# L9963E_BMS_IC.net
KiCad netlist of a schematic drawn in Altium Designer
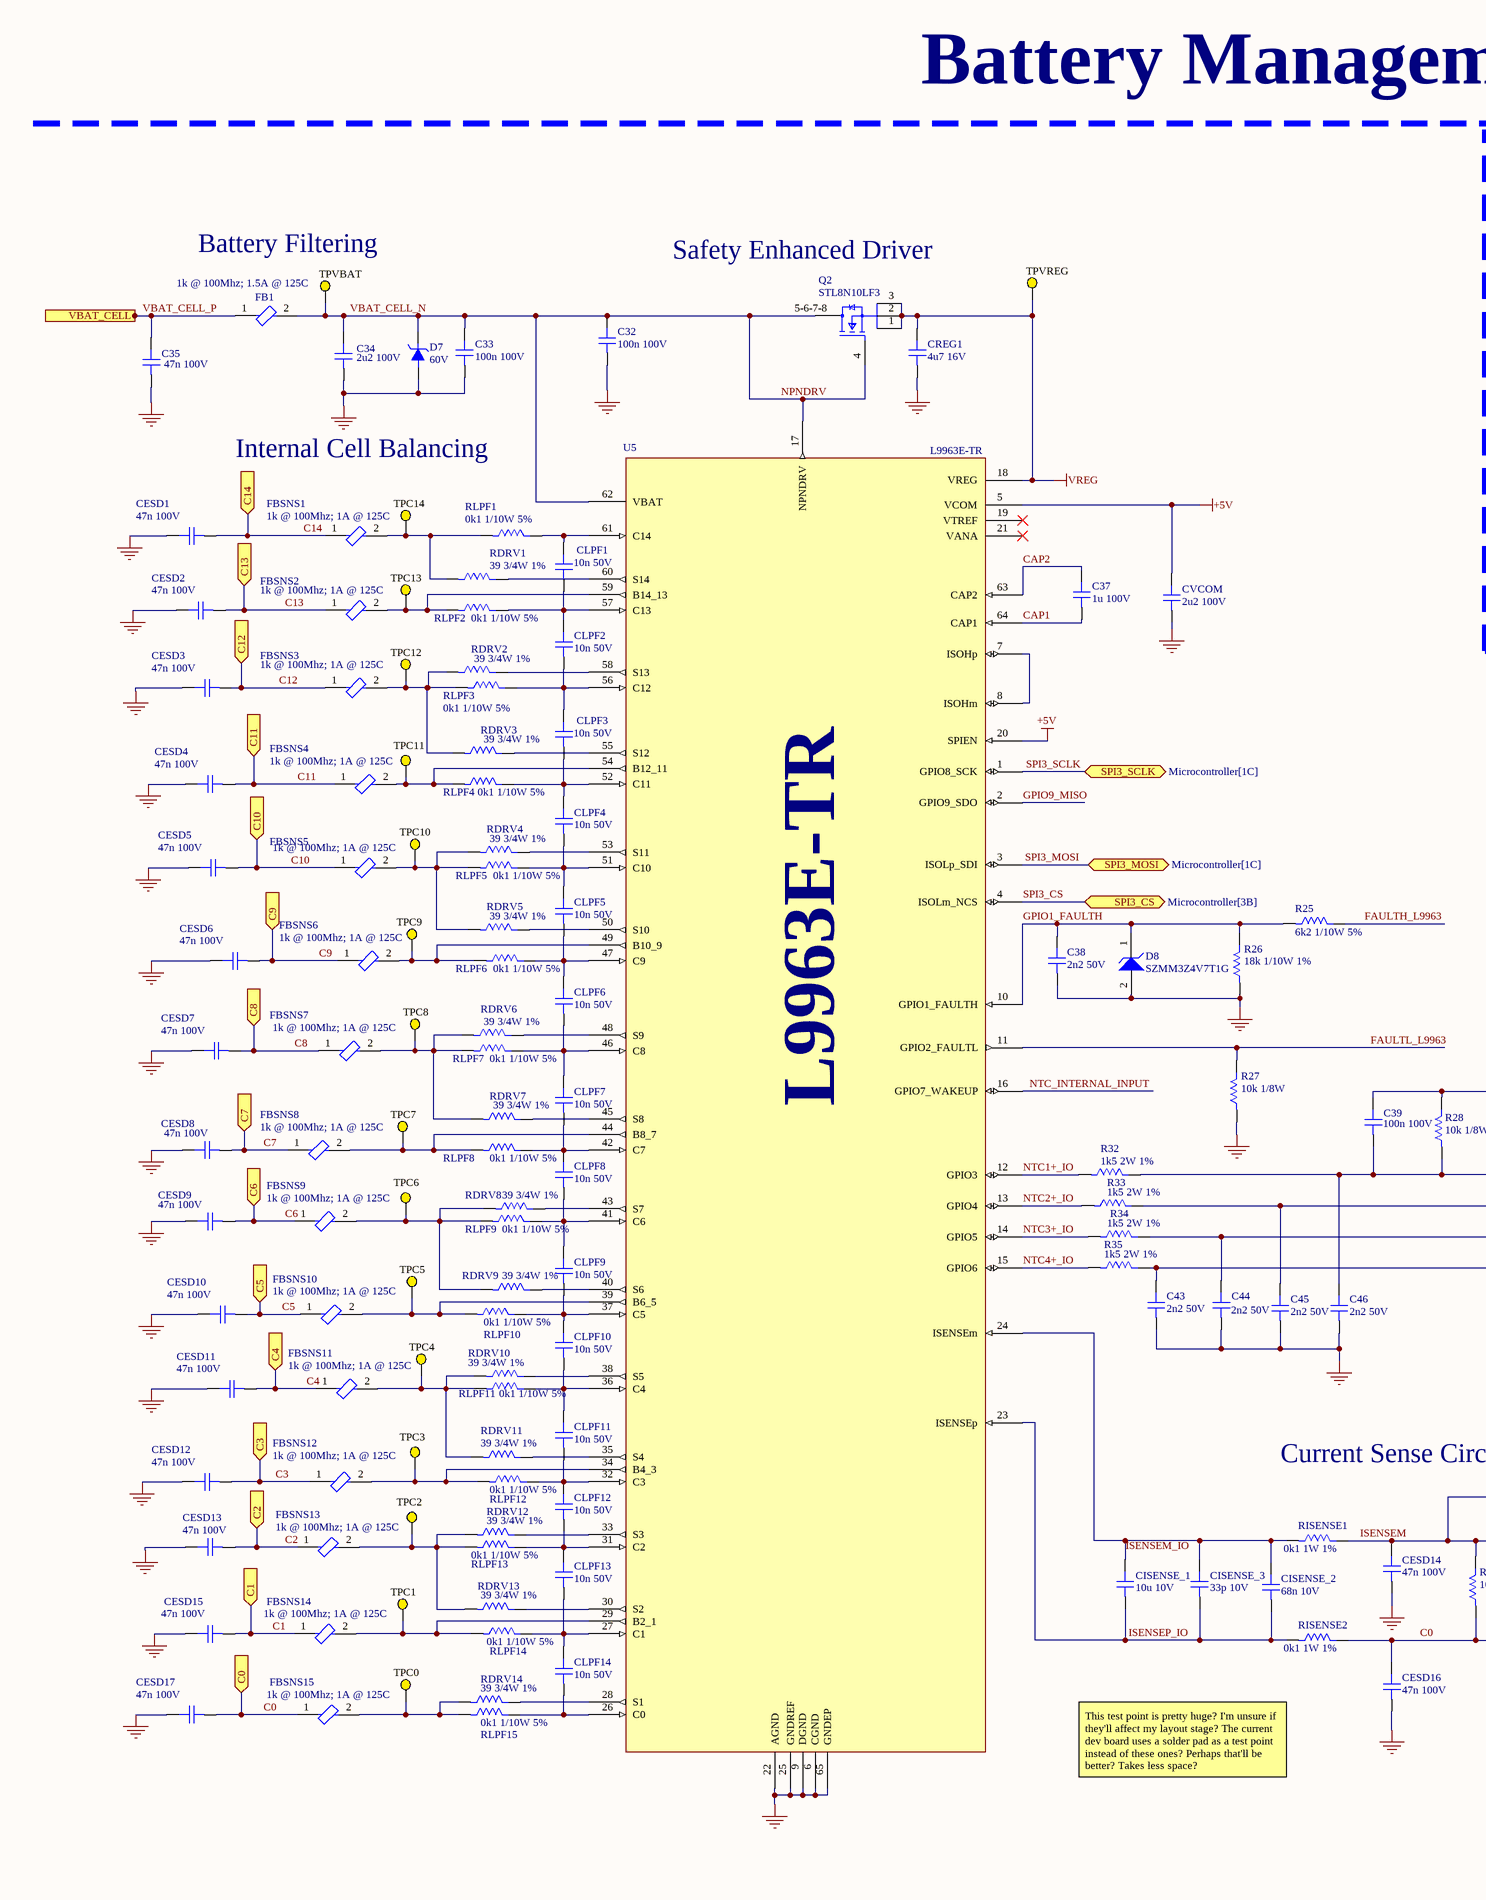
[diagram p0: L9963E_BMS_IC.SchDoc, left]
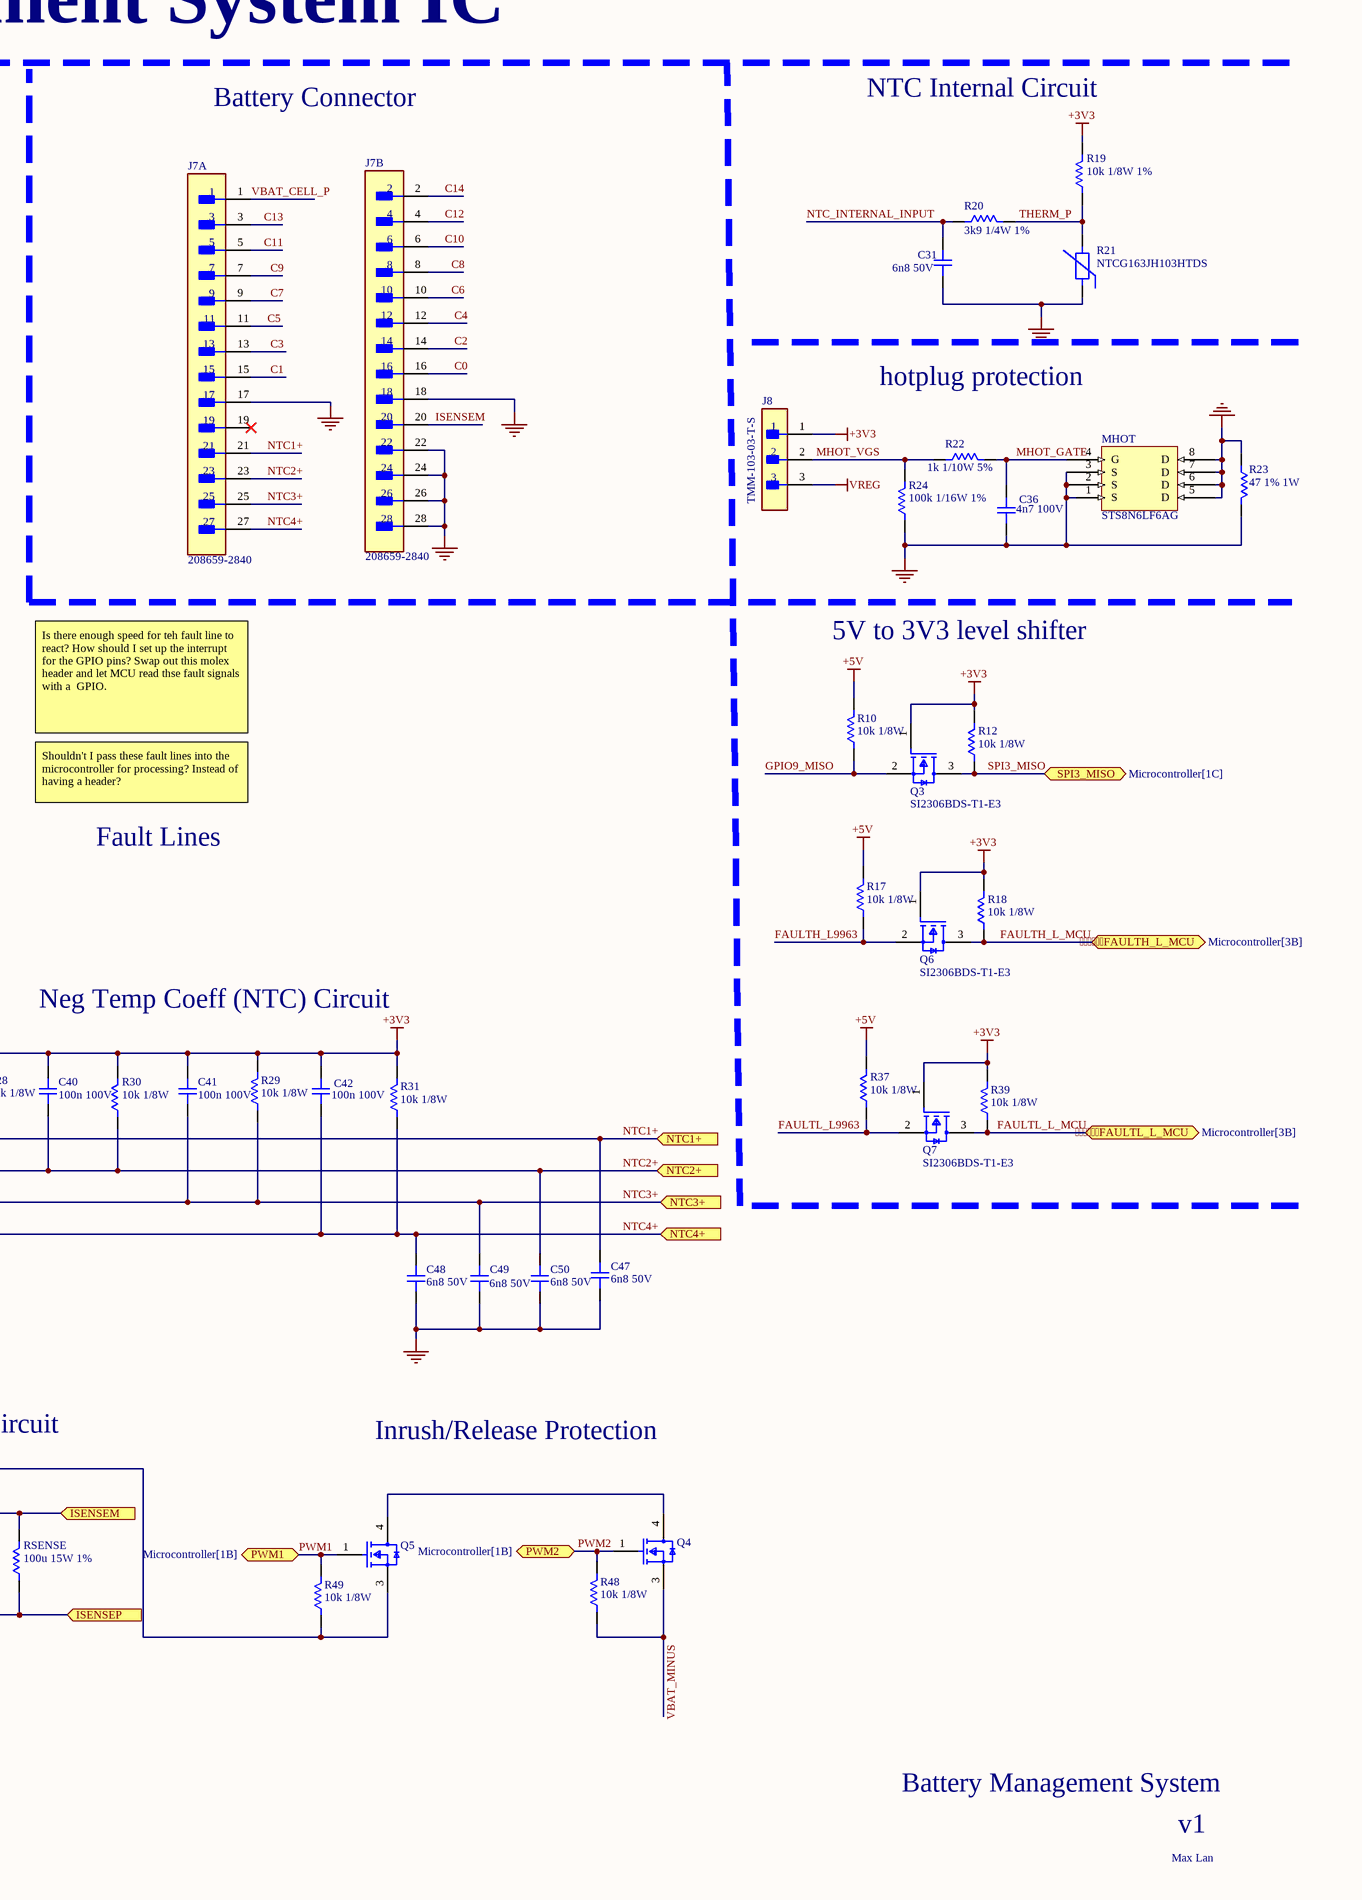
[diagram p1: L9963E_BMS_IC.SchDoc, right]

(export (version "E")
  (design (tool "Eeschema 10.0.6"))
  (components
    (comp (ref "C31")
      (value "6n8 50V")
      (footprint "CAP_0603")
      (fields
        (field (name "MANUFACTURER") "KYOCERA AVX")
        (field (name "MANUFACTURER PART NUMBER") "06035C682MAT2A")
      )
      (libsource (lib "Schematic-Lib-PhilsLab") (part "06035C682MAT2A"))
    )
    (comp (ref "C32")
      (value "100n 100V")
      (footprint "CAP_0603")
      (description "Multilayer Ceramic Capacitors MLCC - SMD/SMT 100V 0.1uF 0603 X7R 10% AECQ2")
      (fields
        (field (name "MANUFACTURER") "TAIYO YUDEN")
        (field (name "MANUFACTURER PART NUMBER") "MAJCH168BB7104KTEA01")
      )
      (libsource (lib "Schematic-Lib-PhilsLab") (part "MAJCH168BB7104KTEA01"))
    )
    (comp (ref "C33")
      (value "100n 100V")
      (footprint "CAP_0603")
      (description "Multilayer Ceramic Capacitors MLCC - SMD/SMT 100V 0.1uF 0603 X7R 10% AECQ2")
      (fields
        (field (name "MANUFACTURER") "TAIYO YUDEN")
        (field (name "MANUFACTURER PART NUMBER") "MAJCH168BB7104KTEA01")
      )
      (libsource (lib "Schematic-Lib-PhilsLab") (part "MAJCH168BB7104KTEA01"))
    )
    (comp (ref "C34")
      (value "2u2 100V")
      (footprint "CAP_1210")
      (description "Multilayer Ceramic Capacitors MLCC - SMD/SMT 100V 2.2uF X7R 1210 5% AEC-Q200")
      (fields
        (field (name "MANUFACTURER") "KEMET")
        (field (name "MANUFACTURER PART NUMBER") "C1210C225J1RACAUTO")
      )
      (libsource (lib "Schematic-Lib-PhilsLab") (part "C1210C225J1RACAUTO"))
    )
    (comp (ref "C35")
      (value "47n 100V")
      (footprint "CAP_0603")
      (description "Multilayer Ceramic Capacitors MLCC - SMD/SMT 100V 0.047uF X7R 0603 5%")
      (fields
        (field (name "MANUFACTURER") "KEMET")
        (field (name "MANUFACTURER PART NUMBER") "C0603C473J1RACTU")
      )
      (libsource (lib "Schematic-Lib-PhilsLab") (part "C0603C473J1RACTU"))
    )
    (comp (ref "C36")
      (value "4n7 100V")
      (footprint "CAP_0603")
      (description "Multilayer Ceramic Capacitors MLCC - SMD/SMT CGA 0603 100V 4700pF X7R 10% AEC-Q200")
      (fields
        (field (name "MANUFACTURER") "TDK")
        (field (name "MANUFACTURER PART NUMBER") "CGA3E2X7R2A472K080AA")
      )
      (libsource (lib "Schematic-Lib-PhilsLab") (part "CGA3E2X7R2A472K080AA"))
    )
    (comp (ref "C37")
      (value "1u 100V")
      (footprint "CAP_0603")
      (description "MLCC - SMD/SMT Commercial Grade,MLCC,0603,X7R,100V,1uF,+/-10%,0.8mm")
      (libsource (lib "Schematic-Lib-PhilsLab") (part "C1608X7R2A105K080AC"))
    )
    (comp (ref "C38")
      (value "2n2 50V")
      (footprint "CAP_0603")
      (description "Multilayer Ceramic Capacitors MLCC - SMD/SMT 50V 2200pF X7R 0603 10% AEC-Q200")
      (fields
        (field (name "MANUFACTURER") "KYOCERA AVX")
        (field (name "MANUFACTURER PART NUMBER") "KAM15AR71H222KT")
      )
      (libsource (lib "Schematic-Lib-PhilsLab") (part "KAM15AR71H222KT"))
    )
    (comp (ref "C39")
      (value "100n 100V")
      (footprint "CAP_0603")
      (description "Multilayer Ceramic Capacitors MLCC - SMD/SMT 100V 0.1uF 0603 X7R 10% AECQ2")
      (fields
        (field (name "MANUFACTURER") "TAIYO YUDEN")
        (field (name "MANUFACTURER PART NUMBER") "MAJCH168BB7104KTEA01")
      )
      (libsource (lib "Schematic-Lib-PhilsLab") (part "MAJCH168BB7104KTEA01"))
    )
    (comp (ref "C40")
      (value "100n 100V")
      (footprint "CAP_0603")
      (description "Multilayer Ceramic Capacitors MLCC - SMD/SMT 100V 0.1uF 0603 X7R 10% AECQ2")
      (fields
        (field (name "MANUFACTURER") "TAIYO YUDEN")
        (field (name "MANUFACTURER PART NUMBER") "MAJCH168BB7104KTEA01")
      )
      (libsource (lib "Schematic-Lib-PhilsLab") (part "MAJCH168BB7104KTEA01"))
    )
    (comp (ref "C41")
      (value "100n 100V")
      (footprint "CAP_0603")
      (description "Multilayer Ceramic Capacitors MLCC - SMD/SMT 100V 0.1uF 0603 X7R 10% AECQ2")
      (fields
        (field (name "MANUFACTURER") "TAIYO YUDEN")
        (field (name "MANUFACTURER PART NUMBER") "MAJCH168BB7104KTEA01")
      )
      (libsource (lib "Schematic-Lib-PhilsLab") (part "MAJCH168BB7104KTEA01"))
    )
    (comp (ref "C42")
      (value "100n 100V")
      (footprint "CAP_0603")
      (description "Multilayer Ceramic Capacitors MLCC - SMD/SMT 100V 0.1uF 0603 X7R 10% AECQ2")
      (fields
        (field (name "MANUFACTURER") "TAIYO YUDEN")
        (field (name "MANUFACTURER PART NUMBER") "MAJCH168BB7104KTEA01")
      )
      (libsource (lib "Schematic-Lib-PhilsLab") (part "MAJCH168BB7104KTEA01"))
    )
    (comp (ref "C43")
      (value "2n2 50V")
      (footprint "CAP_0603")
      (description "Multilayer Ceramic Capacitors MLCC - SMD/SMT 50V 2200pF X7R 0603 10% AEC-Q200")
      (fields
        (field (name "MANUFACTURER") "KYOCERA AVX")
        (field (name "MANUFACTURER PART NUMBER") "KAM15AR71H222KT")
      )
      (libsource (lib "Schematic-Lib-PhilsLab") (part "KAM15AR71H222KT"))
    )
    (comp (ref "C44")
      (value "2n2 50V")
      (footprint "CAP_0603")
      (description "Multilayer Ceramic Capacitors MLCC - SMD/SMT 50V 2200pF X7R 0603 10% AEC-Q200")
      (fields
        (field (name "MANUFACTURER") "KYOCERA AVX")
        (field (name "MANUFACTURER PART NUMBER") "KAM15AR71H222KT")
      )
      (libsource (lib "Schematic-Lib-PhilsLab") (part "KAM15AR71H222KT"))
    )
    (comp (ref "C45")
      (value "2n2 50V")
      (footprint "CAP_0603")
      (description "Multilayer Ceramic Capacitors MLCC - SMD/SMT 50V 2200pF X7R 0603 10% AEC-Q200")
      (fields
        (field (name "MANUFACTURER") "KYOCERA AVX")
        (field (name "MANUFACTURER PART NUMBER") "KAM15AR71H222KT")
      )
      (libsource (lib "Schematic-Lib-PhilsLab") (part "KAM15AR71H222KT"))
    )
    (comp (ref "C46")
      (value "2n2 50V")
      (footprint "CAP_0603")
      (description "Multilayer Ceramic Capacitors MLCC - SMD/SMT 50V 2200pF X7R 0603 10% AEC-Q200")
      (fields
        (field (name "MANUFACTURER") "KYOCERA AVX")
        (field (name "MANUFACTURER PART NUMBER") "KAM15AR71H222KT")
      )
      (libsource (lib "Schematic-Lib-PhilsLab") (part "KAM15AR71H222KT"))
    )
    (comp (ref "C47")
      (value "6n8 50V")
      (footprint "CAP_0603")
      (fields
        (field (name "MANUFACTURER") "KYOCERA AVX")
        (field (name "MANUFACTURER PART NUMBER") "06035C682MAT2A")
      )
      (libsource (lib "Schematic-Lib-PhilsLab") (part "06035C682MAT2A"))
    )
    (comp (ref "C48")
      (value "6n8 50V")
      (footprint "CAP_0603")
      (fields
        (field (name "MANUFACTURER") "KYOCERA AVX")
        (field (name "MANUFACTURER PART NUMBER") "06035C682MAT2A")
      )
      (libsource (lib "Schematic-Lib-PhilsLab") (part "06035C682MAT2A"))
    )
    (comp (ref "C49")
      (value "6n8 50V")
      (footprint "CAP_0603")
      (fields
        (field (name "MANUFACTURER") "KYOCERA AVX")
        (field (name "MANUFACTURER PART NUMBER") "06035C682MAT2A")
      )
      (libsource (lib "Schematic-Lib-PhilsLab") (part "06035C682MAT2A"))
    )
    (comp (ref "C50")
      (value "6n8 50V")
      (footprint "CAP_0603")
      (fields
        (field (name "MANUFACTURER") "KYOCERA AVX")
        (field (name "MANUFACTURER PART NUMBER") "06035C682MAT2A")
      )
      (libsource (lib "Schematic-Lib-PhilsLab") (part "06035C682MAT2A"))
    )
    (comp (ref "CESD1")
      (value "47n 100V")
      (footprint "CAP_0603")
      (description "Multilayer Ceramic Capacitors MLCC - SMD/SMT 100V 0.047uF X7R 0603 5%")
      (fields
        (field (name "MANUFACTURER") "KEMET")
        (field (name "MANUFACTURER PART NUMBER") "C0603C473J1RACTU")
      )
      (libsource (lib "Schematic-Lib-PhilsLab") (part "C0603C473J1RACTU"))
    )
    (comp (ref "CESD2")
      (value "47n 100V")
      (footprint "CAP_0603")
      (description "Multilayer Ceramic Capacitors MLCC - SMD/SMT 100V 0.047uF X7R 0603 5%")
      (fields
        (field (name "MANUFACTURER") "KEMET")
        (field (name "MANUFACTURER PART NUMBER") "C0603C473J1RACTU")
      )
      (libsource (lib "Schematic-Lib-PhilsLab") (part "C0603C473J1RACTU"))
    )
    (comp (ref "CESD3")
      (value "47n 100V")
      (footprint "CAP_0603")
      (description "Multilayer Ceramic Capacitors MLCC - SMD/SMT 100V 0.047uF X7R 0603 5%")
      (fields
        (field (name "MANUFACTURER") "KEMET")
        (field (name "MANUFACTURER PART NUMBER") "C0603C473J1RACTU")
      )
      (libsource (lib "Schematic-Lib-PhilsLab") (part "C0603C473J1RACTU"))
    )
    (comp (ref "CESD4")
      (value "47n 100V")
      (footprint "CAP_0603")
      (description "Multilayer Ceramic Capacitors MLCC - SMD/SMT 100V 0.047uF X7R 0603 5%")
      (fields
        (field (name "MANUFACTURER") "KEMET")
        (field (name "MANUFACTURER PART NUMBER") "C0603C473J1RACTU")
      )
      (libsource (lib "Schematic-Lib-PhilsLab") (part "C0603C473J1RACTU"))
    )
    (comp (ref "CESD5")
      (value "47n 100V")
      (footprint "CAP_0603")
      (description "Multilayer Ceramic Capacitors MLCC - SMD/SMT 100V 0.047uF X7R 0603 5%")
      (fields
        (field (name "MANUFACTURER") "KEMET")
        (field (name "MANUFACTURER PART NUMBER") "C0603C473J1RACTU")
      )
      (libsource (lib "Schematic-Lib-PhilsLab") (part "C0603C473J1RACTU"))
    )
    (comp (ref "CESD6")
      (value "47n 100V")
      (footprint "CAP_0603")
      (description "Multilayer Ceramic Capacitors MLCC - SMD/SMT 100V 0.047uF X7R 0603 5%")
      (fields
        (field (name "MANUFACTURER") "KEMET")
        (field (name "MANUFACTURER PART NUMBER") "C0603C473J1RACTU")
      )
      (libsource (lib "Schematic-Lib-PhilsLab") (part "C0603C473J1RACTU"))
    )
    (comp (ref "CESD7")
      (value "47n 100V")
      (footprint "CAP_0603")
      (description "Multilayer Ceramic Capacitors MLCC - SMD/SMT 100V 0.047uF X7R 0603 5%")
      (fields
        (field (name "MANUFACTURER") "KEMET")
        (field (name "MANUFACTURER PART NUMBER") "C0603C473J1RACTU")
      )
      (libsource (lib "Schematic-Lib-PhilsLab") (part "C0603C473J1RACTU"))
    )
    (comp (ref "CESD8")
      (value "47n 100V")
      (footprint "CAP_0603")
      (description "Multilayer Ceramic Capacitors MLCC - SMD/SMT 100V 0.047uF X7R 0603 5%")
      (fields
        (field (name "MANUFACTURER") "KEMET")
        (field (name "MANUFACTURER PART NUMBER") "C0603C473J1RACTU")
      )
      (libsource (lib "Schematic-Lib-PhilsLab") (part "C0603C473J1RACTU"))
    )
    (comp (ref "CESD9")
      (value "47n 100V")
      (footprint "CAP_0603")
      (description "Multilayer Ceramic Capacitors MLCC - SMD/SMT 100V 0.047uF X7R 0603 5%")
      (fields
        (field (name "MANUFACTURER") "KEMET")
        (field (name "MANUFACTURER PART NUMBER") "C0603C473J1RACTU")
      )
      (libsource (lib "Schematic-Lib-PhilsLab") (part "C0603C473J1RACTU"))
    )
    (comp (ref "CESD10")
      (value "47n 100V")
      (footprint "CAP_0603")
      (description "Multilayer Ceramic Capacitors MLCC - SMD/SMT 100V 0.047uF X7R 0603 5%")
      (fields
        (field (name "MANUFACTURER") "KEMET")
        (field (name "MANUFACTURER PART NUMBER") "C0603C473J1RACTU")
      )
      (libsource (lib "Schematic-Lib-PhilsLab") (part "C0603C473J1RACTU"))
    )
    (comp (ref "CESD11")
      (value "47n 100V")
      (footprint "CAP_0603")
      (description "Multilayer Ceramic Capacitors MLCC - SMD/SMT 100V 0.047uF X7R 0603 5%")
      (fields
        (field (name "MANUFACTURER") "KEMET")
        (field (name "MANUFACTURER PART NUMBER") "C0603C473J1RACTU")
      )
      (libsource (lib "Schematic-Lib-PhilsLab") (part "C0603C473J1RACTU"))
    )
    (comp (ref "CESD12")
      (value "47n 100V")
      (footprint "CAP_0603")
      (description "Multilayer Ceramic Capacitors MLCC - SMD/SMT 100V 0.047uF X7R 0603 5%")
      (fields
        (field (name "MANUFACTURER") "KEMET")
        (field (name "MANUFACTURER PART NUMBER") "C0603C473J1RACTU")
      )
      (libsource (lib "Schematic-Lib-PhilsLab") (part "C0603C473J1RACTU"))
    )
    (comp (ref "CESD13")
      (value "47n 100V")
      (footprint "CAP_0603")
      (description "Multilayer Ceramic Capacitors MLCC - SMD/SMT 100V 0.047uF X7R 0603 5%")
      (fields
        (field (name "MANUFACTURER") "KEMET")
        (field (name "MANUFACTURER PART NUMBER") "C0603C473J1RACTU")
      )
      (libsource (lib "Schematic-Lib-PhilsLab") (part "C0603C473J1RACTU"))
    )
    (comp (ref "CESD14")
      (value "47n 100V")
      (footprint "CAP_0603")
      (description "Multilayer Ceramic Capacitors MLCC - SMD/SMT 100V 0.047uF X7R 0603 5%")
      (fields
        (field (name "MANUFACTURER") "KEMET")
        (field (name "MANUFACTURER PART NUMBER") "C0603C473J1RACTU")
      )
      (libsource (lib "Schematic-Lib-PhilsLab") (part "C0603C473J1RACTU"))
    )
    (comp (ref "CESD15")
      (value "47n 100V")
      (footprint "CAP_0603")
      (description "Multilayer Ceramic Capacitors MLCC - SMD/SMT 100V 0.047uF X7R 0603 5%")
      (fields
        (field (name "MANUFACTURER") "KEMET")
        (field (name "MANUFACTURER PART NUMBER") "C0603C473J1RACTU")
      )
      (libsource (lib "Schematic-Lib-PhilsLab") (part "C0603C473J1RACTU"))
    )
    (comp (ref "CESD16")
      (value "47n 100V")
      (footprint "CAP_0603")
      (description "Multilayer Ceramic Capacitors MLCC - SMD/SMT 100V 0.047uF X7R 0603 5%")
      (fields
        (field (name "MANUFACTURER") "KEMET")
        (field (name "MANUFACTURER PART NUMBER") "C0603C473J1RACTU")
      )
      (libsource (lib "Schematic-Lib-PhilsLab") (part "C0603C473J1RACTU"))
    )
    (comp (ref "CESD17")
      (value "47n 100V")
      (footprint "CAP_0603")
      (description "Multilayer Ceramic Capacitors MLCC - SMD/SMT 100V 0.047uF X7R 0603 5%")
      (fields
        (field (name "MANUFACTURER") "KEMET")
        (field (name "MANUFACTURER PART NUMBER") "C0603C473J1RACTU")
      )
      (libsource (lib "Schematic-Lib-PhilsLab") (part "C0603C473J1RACTU"))
    )
    (comp (ref "CISENSE_1")
      (value "10u 10V")
      (footprint "CAP_0603")
      (description "Multilayer Ceramic Capacitors MLCC - SMD/SMT 10 uF 10 VDC 10% 0603 X7R")
      (fields
        (field (name "MANUFACTURER") "Murata Electronics")
        (field (name "MANUFACTURER PART NUMBER") "GRM188Z71A106KA73D")
      )
      (libsource (lib "Schematic-Lib-PhilsLab") (part "GRM188Z71A106KA73D"))
    )
    (comp (ref "CISENSE_2")
      (value "68n 10V")
      (footprint "CAP_0603")
      (description "Multilayer Ceramic Capacitors MLCC - SMD/SMT 0603 0.068uF 10volts X7R 5%")
      (fields
        (field (name "MANUFACTURER") "Vishay/Vitramon")
        (field (name "MANUFACTURER PART NUMBER") "VJ0603Y683JXQCW1BC")
      )
      (libsource (lib "Schematic-Lib-PhilsLab") (part "VJ0603Y683JXQCW1BC"))
    )
    (comp (ref "CISENSE_3")
      (value "33p 10V")
      (footprint "CAP_0402")
      (description "Multilayer Ceramic Capacitors MLCC - SMD/SMT 10V 33pF X7R 0402 10%")
      (fields
        (field (name "MANUFACTURER") "KYOCERA AVX")
        (field (name "MANUFACTURER PART NUMBER") "KGM05AR71A330KH")
      )
      (libsource (lib "Schematic-Lib-PhilsLab") (part "KGM05AR71A330KH"))
    )
    (comp (ref "CLPF1")
      (value "10n 50V")
      (footprint "CAP_0603")
      (description "Multilayer Ceramic Capacitors MLCC - SMD/SMT Automotive MLCC 0603, 10nF, 5%, X7R, 50VDC")
      (fields
        (field (name "MANUFACTURER") "KYOCERA AVX")
        (field (name "MANUFACTURER PART NUMBER") "KAF15AR71H103JM")
      )
      (libsource (lib "Schematic-Lib-PhilsLab") (part "KAF15AR71H103JM"))
    )
    (comp (ref "CLPF2")
      (value "10n 50V")
      (footprint "CAP_0603")
      (description "Multilayer Ceramic Capacitors MLCC - SMD/SMT Automotive MLCC 0603, 10nF, 5%, X7R, 50VDC")
      (fields
        (field (name "MANUFACTURER") "KYOCERA AVX")
        (field (name "MANUFACTURER PART NUMBER") "KAF15AR71H103JM")
      )
      (libsource (lib "Schematic-Lib-PhilsLab") (part "KAF15AR71H103JM"))
    )
    (comp (ref "CLPF3")
      (value "10n 50V")
      (footprint "CAP_0603")
      (description "Multilayer Ceramic Capacitors MLCC - SMD/SMT Automotive MLCC 0603, 10nF, 5%, X7R, 50VDC")
      (fields
        (field (name "MANUFACTURER") "KYOCERA AVX")
        (field (name "MANUFACTURER PART NUMBER") "KAF15AR71H103JM")
      )
      (libsource (lib "Schematic-Lib-PhilsLab") (part "KAF15AR71H103JM"))
    )
    (comp (ref "CLPF4")
      (value "10n 50V")
      (footprint "CAP_0603")
      (description "Multilayer Ceramic Capacitors MLCC - SMD/SMT Automotive MLCC 0603, 10nF, 5%, X7R, 50VDC")
      (fields
        (field (name "MANUFACTURER") "KYOCERA AVX")
        (field (name "MANUFACTURER PART NUMBER") "KAF15AR71H103JM")
      )
      (libsource (lib "Schematic-Lib-PhilsLab") (part "KAF15AR71H103JM"))
    )
    (comp (ref "CLPF5")
      (value "10n 50V")
      (footprint "CAP_0603")
      (description "Multilayer Ceramic Capacitors MLCC - SMD/SMT Automotive MLCC 0603, 10nF, 5%, X7R, 50VDC")
      (fields
        (field (name "MANUFACTURER") "KYOCERA AVX")
        (field (name "MANUFACTURER PART NUMBER") "KAF15AR71H103JM")
      )
      (libsource (lib "Schematic-Lib-PhilsLab") (part "KAF15AR71H103JM"))
    )
    (comp (ref "CLPF6")
      (value "10n 50V")
      (footprint "CAP_0603")
      (description "Multilayer Ceramic Capacitors MLCC - SMD/SMT Automotive MLCC 0603, 10nF, 5%, X7R, 50VDC")
      (fields
        (field (name "MANUFACTURER") "KYOCERA AVX")
        (field (name "MANUFACTURER PART NUMBER") "KAF15AR71H103JM")
      )
      (libsource (lib "Schematic-Lib-PhilsLab") (part "KAF15AR71H103JM"))
    )
    (comp (ref "CLPF7")
      (value "10n 50V")
      (footprint "CAP_0603")
      (description "Multilayer Ceramic Capacitors MLCC - SMD/SMT Automotive MLCC 0603, 10nF, 5%, X7R, 50VDC")
      (fields
        (field (name "MANUFACTURER") "KYOCERA AVX")
        (field (name "MANUFACTURER PART NUMBER") "KAF15AR71H103JM")
      )
      (libsource (lib "Schematic-Lib-PhilsLab") (part "KAF15AR71H103JM"))
    )
    (comp (ref "CLPF8")
      (value "10n 50V")
      (footprint "CAP_0603")
      (description "Multilayer Ceramic Capacitors MLCC - SMD/SMT Automotive MLCC 0603, 10nF, 5%, X7R, 50VDC")
      (fields
        (field (name "MANUFACTURER") "KYOCERA AVX")
        (field (name "MANUFACTURER PART NUMBER") "KAF15AR71H103JM")
      )
      (libsource (lib "Schematic-Lib-PhilsLab") (part "KAF15AR71H103JM"))
    )
    (comp (ref "CLPF9")
      (value "10n 50V")
      (footprint "CAP_0603")
      (description "Multilayer Ceramic Capacitors MLCC - SMD/SMT Automotive MLCC 0603, 10nF, 5%, X7R, 50VDC")
      (fields
        (field (name "MANUFACTURER") "KYOCERA AVX")
        (field (name "MANUFACTURER PART NUMBER") "KAF15AR71H103JM")
      )
      (libsource (lib "Schematic-Lib-PhilsLab") (part "KAF15AR71H103JM"))
    )
    (comp (ref "CLPF10")
      (value "10n 50V")
      (footprint "CAP_0603")
      (description "Multilayer Ceramic Capacitors MLCC - SMD/SMT Automotive MLCC 0603, 10nF, 5%, X7R, 50VDC")
      (fields
        (field (name "MANUFACTURER") "KYOCERA AVX")
        (field (name "MANUFACTURER PART NUMBER") "KAF15AR71H103JM")
      )
      (libsource (lib "Schematic-Lib-PhilsLab") (part "KAF15AR71H103JM"))
    )
    (comp (ref "CLPF11")
      (value "10n 50V")
      (footprint "CAP_0603")
      (description "Multilayer Ceramic Capacitors MLCC - SMD/SMT Automotive MLCC 0603, 10nF, 5%, X7R, 50VDC")
      (fields
        (field (name "MANUFACTURER") "KYOCERA AVX")
        (field (name "MANUFACTURER PART NUMBER") "KAF15AR71H103JM")
      )
      (libsource (lib "Schematic-Lib-PhilsLab") (part "KAF15AR71H103JM"))
    )
    (comp (ref "CLPF12")
      (value "10n 50V")
      (footprint "CAP_0603")
      (description "Multilayer Ceramic Capacitors MLCC - SMD/SMT Automotive MLCC 0603, 10nF, 5%, X7R, 50VDC")
      (fields
        (field (name "MANUFACTURER") "KYOCERA AVX")
        (field (name "MANUFACTURER PART NUMBER") "KAF15AR71H103JM")
      )
      (libsource (lib "Schematic-Lib-PhilsLab") (part "KAF15AR71H103JM"))
    )
    (comp (ref "CLPF13")
      (value "10n 50V")
      (footprint "CAP_0603")
      (description "Multilayer Ceramic Capacitors MLCC - SMD/SMT Automotive MLCC 0603, 10nF, 5%, X7R, 50VDC")
      (fields
        (field (name "MANUFACTURER") "KYOCERA AVX")
        (field (name "MANUFACTURER PART NUMBER") "KAF15AR71H103JM")
      )
      (libsource (lib "Schematic-Lib-PhilsLab") (part "KAF15AR71H103JM"))
    )
    (comp (ref "CLPF14")
      (value "10n 50V")
      (footprint "CAP_0603")
      (description "Multilayer Ceramic Capacitors MLCC - SMD/SMT Automotive MLCC 0603, 10nF, 5%, X7R, 50VDC")
      (fields
        (field (name "MANUFACTURER") "KYOCERA AVX")
        (field (name "MANUFACTURER PART NUMBER") "KAF15AR71H103JM")
      )
      (libsource (lib "Schematic-Lib-PhilsLab") (part "KAF15AR71H103JM"))
    )
    (comp (ref "CREG1")
      (value "4u7 16V")
      (footprint "CAP_0805")
      (description "Multilayer Ceramic Capacitors MLCC - SMD/SMT 16 V 4.7 uF 0805 X7R 5 % AECQ200")
      (fields
        (field (name "MANUFACTURER") "KEMET")
        (field (name "MANUFACTURER PART NUMBER") "C0805C475J4RACAUTO7210")
      )
      (libsource (lib "Schematic-Lib-PhilsLab") (part "C0805C475J4RACAUTO7210"))
    )
    (comp (ref "CVCOM")
      (value "2u2 100V")
      (footprint "CAP_1210")
      (description "Multilayer Ceramic Capacitors MLCC - SMD/SMT 100V 2.2uF X7R 1210 5% AEC-Q200")
      (fields
        (field (name "MANUFACTURER") "KEMET")
        (field (name "MANUFACTURER PART NUMBER") "C1210C225J1RACAUTO")
      )
      (libsource (lib "Schematic-Lib-PhilsLab") (part "C1210C225J1RACAUTO"))
    )
    (comp (ref "D7")
      (value "60V")
      (footprint "5.0SMDJ60A")
      (description "ESD 保護二極體 / TVS 二極體 60V 5KW 5% UNI DO-214AB (SMC)")
      (libsource (lib "Schematic-Lib-PhilsLab") (part "5.0SMDJ60A"))
    )
    (comp (ref "D8")
      (value "SZMM3Z4V7T1G")
      (footprint "ONSC-SOD-323-2-477-02_V")
      (description "Zener Voltage Regulator, 300 mW, 2-Pin SOD-323, Pb-Free, Tape and Reel")
      (fields (field (name "MANUFACTURER") "On Semiconductor"))
      (libsource (lib "Altium Content Vault") (part "ONSC-K1A2-2"))
    )
    (comp (ref "FB1")
      (value "1k @ 100Mhz; 1.5A @ 125C")
      (footprint "FP-MPZ2012-MFG")
      (description "FERRITE BEAD 1 KOHM 0805 1LN")
      (fields (field (name "TOLERANCE") "25%"))
      (libsource (lib "Altium Content Vault") (part "5f30dd21d616792df468990f7003faa"))
    )
    (comp (ref "FBSNS1")
      (value "1k @ 100Mhz; 1A @ 125C")
      (footprint "FP-MPZ2012-MFG")
      (description "FERRITE BEAD 1 KOHM 0805 1LN")
      (fields (field (name "TOLERANCE") "25%"))
      (libsource (lib "Altium Content Vault") (part "5f30dd21d616792df468990f7003faa"))
    )
    (comp (ref "FBSNS2")
      (value "1k @ 100Mhz; 1A @ 125C")
      (footprint "FP-MPZ2012-MFG")
      (description "FERRITE BEAD 1 KOHM 0805 1LN")
      (fields (field (name "TOLERANCE") "25%"))
      (libsource (lib "Altium Content Vault") (part "5f30dd21d616792df468990f7003faa"))
    )
    (comp (ref "FBSNS3")
      (value "1k @ 100Mhz; 1A @ 125C")
      (footprint "FP-MPZ2012-MFG")
      (description "FERRITE BEAD 1 KOHM 0805 1LN")
      (fields (field (name "TOLERANCE") "25%"))
      (libsource (lib "Altium Content Vault") (part "5f30dd21d616792df468990f7003faa"))
    )
    (comp (ref "FBSNS4")
      (value "1k @ 100Mhz; 1A @ 125C")
      (footprint "FP-MPZ2012-MFG")
      (description "FERRITE BEAD 1 KOHM 0805 1LN")
      (fields (field (name "TOLERANCE") "25%"))
      (libsource (lib "Altium Content Vault") (part "5f30dd21d616792df468990f7003faa"))
    )
    (comp (ref "FBSNS5")
      (value "1k @ 100Mhz; 1A @ 125C")
      (footprint "FP-MPZ2012-MFG")
      (description "FERRITE BEAD 1 KOHM 0805 1LN")
      (fields (field (name "TOLERANCE") "25%"))
      (libsource (lib "Altium Content Vault") (part "5f30dd21d616792df468990f7003faa"))
    )
    (comp (ref "FBSNS6")
      (value "1k @ 100Mhz; 1A @ 125C")
      (footprint "FP-MPZ2012-MFG")
      (description "FERRITE BEAD 1 KOHM 0805 1LN")
      (fields (field (name "TOLERANCE") "25%"))
      (libsource (lib "Altium Content Vault") (part "5f30dd21d616792df468990f7003faa"))
    )
    (comp (ref "FBSNS7")
      (value "1k @ 100Mhz; 1A @ 125C")
      (footprint "FP-MPZ2012-MFG")
      (description "FERRITE BEAD 1 KOHM 0805 1LN")
      (fields (field (name "TOLERANCE") "25%"))
      (libsource (lib "Altium Content Vault") (part "5f30dd21d616792df468990f7003faa"))
    )
    (comp (ref "FBSNS8")
      (value "1k @ 100Mhz; 1A @ 125C")
      (footprint "FP-MPZ2012-MFG")
      (description "FERRITE BEAD 1 KOHM 0805 1LN")
      (fields (field (name "TOLERANCE") "25%"))
      (libsource (lib "Altium Content Vault") (part "5f30dd21d616792df468990f7003faa"))
    )
    (comp (ref "FBSNS9")
      (value "1k @ 100Mhz; 1A @ 125C")
      (footprint "FP-MPZ2012-MFG")
      (description "FERRITE BEAD 1 KOHM 0805 1LN")
      (fields (field (name "TOLERANCE") "25%"))
      (libsource (lib "Altium Content Vault") (part "5f30dd21d616792df468990f7003faa"))
    )
    (comp (ref "FBSNS10")
      (value "1k @ 100Mhz; 1A @ 125C")
      (footprint "FP-MPZ2012-MFG")
      (description "FERRITE BEAD 1 KOHM 0805 1LN")
      (fields (field (name "TOLERANCE") "25%"))
      (libsource (lib "Altium Content Vault") (part "5f30dd21d616792df468990f7003faa"))
    )
    (comp (ref "FBSNS11")
      (value "1k @ 100Mhz; 1A @ 125C")
      (footprint "FP-MPZ2012-MFG")
      (description "FERRITE BEAD 1 KOHM 0805 1LN")
      (fields (field (name "TOLERANCE") "25%"))
      (libsource (lib "Altium Content Vault") (part "5f30dd21d616792df468990f7003faa"))
    )
    (comp (ref "FBSNS12")
      (value "1k @ 100Mhz; 1A @ 125C")
      (footprint "FP-MPZ2012-MFG")
      (description "FERRITE BEAD 1 KOHM 0805 1LN")
      (fields (field (name "TOLERANCE") "25%"))
      (libsource (lib "Altium Content Vault") (part "5f30dd21d616792df468990f7003faa"))
    )
    (comp (ref "FBSNS13")
      (value "1k @ 100Mhz; 1A @ 125C")
      (footprint "FP-MPZ2012-MFG")
      (description "FERRITE BEAD 1 KOHM 0805 1LN")
      (fields (field (name "TOLERANCE") "25%"))
      (libsource (lib "Altium Content Vault") (part "5f30dd21d616792df468990f7003faa"))
    )
    (comp (ref "FBSNS14")
      (value "1k @ 100Mhz; 1A @ 125C")
      (footprint "FP-MPZ2012-MFG")
      (description "FERRITE BEAD 1 KOHM 0805 1LN")
      (fields (field (name "TOLERANCE") "25%"))
      (libsource (lib "Altium Content Vault") (part "5f30dd21d616792df468990f7003faa"))
    )
    (comp (ref "FBSNS15")
      (value "1k @ 100Mhz; 1A @ 125C")
      (footprint "FP-MPZ2012-MFG")
      (description "FERRITE BEAD 1 KOHM 0805 1LN")
      (fields (field (name "TOLERANCE") "25%"))
      (libsource (lib "Altium Content Vault") (part "5f30dd21d616792df468990f7003faa"))
    )
    (comp (ref "J7")
      (value "208659-2840")
      (footprint "FP-208659-2840-MFG")
      (description "IGRID PLUG TH HDR RA GF 28CKT")
      (libsource (lib "Altium Content Vault") (part "99fccea96b099ce48943d56df1187c0"))
    )
    (comp (ref "J8")
      (value "TMM-103-03-T-S")
      (footprint "FP-TMM-103-03-T-S-MFG")
      (description "CONN HEADER VERT 3POS 2MM")
      (libsource (lib "Altium Content Vault") (part "0d3f023dd272f625e17a2be33dea85f"))
    )
    (comp (ref "MHOT")
      (value "STS8N6LF6AG")
      (footprint "STS8N6LF6AG")
      (description "Automotive-grade N-channel 60 V, 21 mΩ typ., 8 A STripFET F6\r\nPower MOSFET in an SO-8 package")
      (libsource (lib "Schematic-Lib-PhilsLab") (part "STS8N6LF6AG"))
    )
    (comp (ref "Q2")
      (value "STL8N10LF3")
      (footprint "FP-PowerFLAT5x6-A0Y5_8231-MFG")
      (description "MOSFET N CH 100V 20A PWRFLT5X6")
      (fields
        (field (name "OCTOPART") "https://octopart.com/stl8n10lf3-stmicroelectronics-28565037")
        (field (name "MANUFACTURER") "STMicroelectronics")
      )
      (libsource (lib "Altium Content Vault") (part "1ea3db3a3c715c577877118b9975f57"))
    )
    (comp (ref "Q3")
      (value "SI2306BDS-T1-E3")
      (footprint "FP-S-03946-IPC_A")
      (description "MOSFET N-CH 30V 3.16A SOT23-3")
      (libsource (lib "Altium Content Vault") (part "0a9ea7c96deaaede766a5b531c28de0"))
    )
    (comp (ref "Q4")
      (value "HUF76629D3ST")
      (footprint "FP-369AS-MFG")
      (description "HUF76629D3ST N-Channel Logic Level UltraFET® Power MOSFET 100V, 20A, 52mΩ")
      (libsource (lib "Altium Content Vault") (part "9dda50919618e2b74f88a68e272f5a4"))
    )
    (comp (ref "Q5")
      (value "HUF76629D3ST")
      (footprint "FP-369AS-MFG")
      (description "HUF76629D3ST N-Channel Logic Level UltraFET® Power MOSFET 100V, 20A, 52mΩ")
      (libsource (lib "Altium Content Vault") (part "9dda50919618e2b74f88a68e272f5a4"))
    )
    (comp (ref "Q6")
      (value "SI2306BDS-T1-E3")
      (footprint "FP-S-03946-IPC_A")
      (description "MOSFET N-CH 30V 3.16A SOT23-3")
      (libsource (lib "Altium Content Vault") (part "0a9ea7c96deaaede766a5b531c28de0"))
    )
    (comp (ref "Q7")
      (value "SI2306BDS-T1-E3")
      (footprint "FP-S-03946-IPC_A")
      (description "MOSFET N-CH 30V 3.16A SOT23-3")
      (libsource (lib "Altium Content Vault") (part "0a9ea7c96deaaede766a5b531c28de0"))
    )
    (comp (ref "R10")
      (value "10k 1/8W")
      (footprint "RES_0603")
      (description "Thick Film Resistors - SMD 10K OHM 1%")
      (fields
        (field (name "MANUFACTURER") "Vishay")
        (field (name "MANUFACTURER PART NUMBER") "CRCW060310K0FKEI")
      )
      (libsource (lib "Schematic-Lib-PhilsLab") (part "CRCW060310K0FKEI"))
    )
    (comp (ref "R12")
      (value "10k 1/8W")
      (footprint "RES_0603")
      (description "Thick Film Resistors - SMD 10K OHM 1%")
      (fields
        (field (name "MANUFACTURER") "Vishay")
        (field (name "MANUFACTURER PART NUMBER") "CRCW060310K0FKEI")
      )
      (libsource (lib "Schematic-Lib-PhilsLab") (part "CRCW060310K0FKEI"))
    )
    (comp (ref "R17")
      (value "10k 1/8W")
      (footprint "RES_0603")
      (description "Thick Film Resistors - SMD 10K OHM 1%")
      (fields
        (field (name "MANUFACTURER") "Vishay")
        (field (name "MANUFACTURER PART NUMBER") "CRCW060310K0FKEI")
      )
      (libsource (lib "Schematic-Lib-PhilsLab") (part "CRCW060310K0FKEI"))
    )
    (comp (ref "R18")
      (value "10k 1/8W")
      (footprint "RES_0603")
      (description "Thick Film Resistors - SMD 10K OHM 1%")
      (fields
        (field (name "MANUFACTURER") "Vishay")
        (field (name "MANUFACTURER PART NUMBER") "CRCW060310K0FKEI")
      )
      (libsource (lib "Schematic-Lib-PhilsLab") (part "CRCW060310K0FKEI"))
    )
    (comp (ref "R19")
      (value "10k 1/8W 1%")
      (footprint "RES_0603")
      (description "Thick Film Resistors - SMD 10K OHM 1%")
      (fields
        (field (name "MANUFACTURER") "Vishay")
        (field (name "MANUFACTURER PART NUMBER") "CRCW060310K0FKEI")
      )
      (libsource (lib "Schematic-Lib-PhilsLab") (part "CRCW060310K0FKEI"))
    )
    (comp (ref "R20")
      (value "3k9 1/4W 1%")
      (footprint "RES_0805")
      (description "Thick Film Resistors - SMD CRCW0805-P 3.9K 1% 50 RT1")
      (fields
        (field (name "MANUFACTURER") "Vishay")
        (field (name "MANUFACTURER PART NUMBER") "CRCW08053K90FHTAP")
      )
      (libsource (lib "Schematic-Lib-PhilsLab") (part "CRCW08053K90FHTAP"))
    )
    (comp (ref "R21")
      (value "NTCG163JH103HTDS")
      (footprint "RES_0603")
      (description "NTC Thermistors 0603 10Kohm 3% Thermistor AEC-Q200")
      (libsource (lib "Schematic-Lib-PhilsLab") (part "NTCG163JH103HTDS"))
    )
    (comp (ref "R22")
      (value "1k 1/10W 5%")
      (footprint "RES_0603")
      (description "Thick Film Resistors - SMD 1 kOhms 1/10 W 75 V 5% 0603 100 PPM / C - 55 C / + 155 C AEC-Q200")
      (fields
        (field (name "MANUFACTURER") "YAGEO")
        (field (name "MANUFACTURER PART NUMBER") "AC0603JR-071KL")
      )
      (libsource (lib "Schematic-Lib-PhilsLab") (part "AC0603JR-071KL"))
    )
    (comp (ref "R23")
      (value "47 1% 1W")
      (footprint "RES_2512")
      (description "Thick Film Resistors - SMD 2512 1% 47ohm Anti-Sulfur AEC-Q200")
      (fields
        (field (name "MANUFACTURER") "Panasonic")
        (field (name "MANUFACTURER PART NUMBER") "ERJ-U1TF47R0U")
      )
      (libsource (lib "Schematic-Lib-PhilsLab") (part "ERJ-U1TF47R0U"))
    )
    (comp (ref "R24")
      (value "100k 1/16W 1%")
      (footprint "RES_0402")
      (description "Thin Film Resistors - SMD 100kOhm,0402,1%,50pp m,63mW,50V")
      (fields
        (field (name "MANUFACTURER") "KOA Speer")
        (field (name "MANUFACTURER PART NUMBER") "RN73H1ETTP1003F50")
      )
      (libsource (lib "Schematic-Lib-PhilsLab") (part "RN73H1ETTP1003F50"))
    )
    (comp (ref "R25")
      (value "6k2 1/10W 5%")
      (footprint "RES_0603")
      (description "Thick Film Resistors - SMD 6.2 kOhms 1/10 W 75 V 5% 0603 100 PPM / C - 55 C / + 155 C AEC-Q200")
      (fields
        (field (name "MANUFACTURER") "YAGEO")
        (field (name "MANUFACTURER PART NUMBER") "AC0603JR-076K2L")
      )
      (libsource (lib "Schematic-Lib-PhilsLab") (part "AC0603JR-076K2L"))
    )
    (comp (ref "R26")
      (value "18k 1/10W 1%")
      (footprint "RES_0603")
      (description "Thick Film Resistors - SMD General Purpose Chip Resistor 0603, 18kOhms, 1%, 1/10W")
      (fields
        (field (name "MANUFACTURER") "YAGEO")
        (field (name "MANUFACTURER PART NUMBER") "RC0603FR-1018KL")
      )
      (libsource (lib "Schematic-Lib-PhilsLab") (part "RC0603FR-1018KL"))
    )
    (comp (ref "R27")
      (value "10k 1/8W")
      (footprint "RES_0603")
      (description "Thick Film Resistors - SMD 10K OHM 1%")
      (fields
        (field (name "MANUFACTURER") "Vishay")
        (field (name "MANUFACTURER PART NUMBER") "CRCW060310K0FKEI")
      )
      (libsource (lib "Schematic-Lib-PhilsLab") (part "CRCW060310K0FKEI"))
    )
    (comp (ref "R28")
      (value "10k 1/8W")
      (footprint "RES_0603")
      (description "Thick Film Resistors - SMD 10K OHM 1%")
      (fields
        (field (name "MANUFACTURER") "Vishay")
        (field (name "MANUFACTURER PART NUMBER") "CRCW060310K0FKEI")
      )
      (libsource (lib "Schematic-Lib-PhilsLab") (part "CRCW060310K0FKEI"))
    )
    (comp (ref "R29")
      (value "10k 1/8W")
      (footprint "RES_0603")
      (description "Thick Film Resistors - SMD 10K OHM 1%")
      (fields
        (field (name "MANUFACTURER") "Vishay")
        (field (name "MANUFACTURER PART NUMBER") "CRCW060310K0FKEI")
      )
      (libsource (lib "Schematic-Lib-PhilsLab") (part "CRCW060310K0FKEI"))
    )
    (comp (ref "R30")
      (value "10k 1/8W")
      (footprint "RES_0603")
      (description "Thick Film Resistors - SMD 10K OHM 1%")
      (fields
        (field (name "MANUFACTURER") "Vishay")
        (field (name "MANUFACTURER PART NUMBER") "CRCW060310K0FKEI")
      )
      (libsource (lib "Schematic-Lib-PhilsLab") (part "CRCW060310K0FKEI"))
    )
    (comp (ref "R31")
      (value "10k 1/8W")
      (footprint "RES_0603")
      (description "Thick Film Resistors - SMD 10K OHM 1%")
      (fields
        (field (name "MANUFACTURER") "Vishay")
        (field (name "MANUFACTURER PART NUMBER") "CRCW060310K0FKEI")
      )
      (libsource (lib "Schematic-Lib-PhilsLab") (part "CRCW060310K0FKEI"))
    )
    (comp (ref "R32")
      (value "1k5 2W 1%")
      (footprint "RES_2010")
      (description "Thick Film Resistors - SMD 3502 1K5 1%")
      (fields
        (field (name "MANUFACTURER") "TE Connectivity")
        (field (name "MANUFACTURER PART NUMBER") "35021K5FT")
      )
      (libsource (lib "Schematic-Lib-PhilsLab") (part "35021K5FT"))
    )
    (comp (ref "R33")
      (value "1k5 2W 1%")
      (footprint "RES_2010")
      (description "Thick Film Resistors - SMD 3502 1K5 1%")
      (fields
        (field (name "MANUFACTURER") "TE Connectivity")
        (field (name "MANUFACTURER PART NUMBER") "35021K5FT")
      )
      (libsource (lib "Schematic-Lib-PhilsLab") (part "35021K5FT"))
    )
    (comp (ref "R34")
      (value "1k5 2W 1%")
      (footprint "RES_2010")
      (description "Thick Film Resistors - SMD 3502 1K5 1%")
      (fields
        (field (name "MANUFACTURER") "TE Connectivity")
        (field (name "MANUFACTURER PART NUMBER") "35021K5FT")
      )
      (libsource (lib "Schematic-Lib-PhilsLab") (part "35021K5FT"))
    )
    (comp (ref "R35")
      (value "1k5 2W 1%")
      (footprint "RES_2010")
      (description "Thick Film Resistors - SMD 3502 1K5 1%")
      (fields
        (field (name "MANUFACTURER") "TE Connectivity")
        (field (name "MANUFACTURER PART NUMBER") "35021K5FT")
      )
      (libsource (lib "Schematic-Lib-PhilsLab") (part "35021K5FT"))
    )
    (comp (ref "R37")
      (value "10k 1/8W")
      (footprint "RES_0603")
      (description "Thick Film Resistors - SMD 10K OHM 1%")
      (fields
        (field (name "MANUFACTURER") "Vishay")
        (field (name "MANUFACTURER PART NUMBER") "CRCW060310K0FKEI")
      )
      (libsource (lib "Schematic-Lib-PhilsLab") (part "CRCW060310K0FKEI"))
    )
    (comp (ref "R39")
      (value "10k 1/8W")
      (footprint "RES_0603")
      (description "Thick Film Resistors - SMD 10K OHM 1%")
      (fields
        (field (name "MANUFACTURER") "Vishay")
        (field (name "MANUFACTURER PART NUMBER") "CRCW060310K0FKEI")
      )
      (libsource (lib "Schematic-Lib-PhilsLab") (part "CRCW060310K0FKEI"))
    )
    (comp (ref "R48")
      (value "10k 1/8W")
      (footprint "RES_0603")
      (description "Thick Film Resistors - SMD 10K OHM 1%")
      (fields
        (field (name "MANUFACTURER") "Vishay")
        (field (name "MANUFACTURER PART NUMBER") "CRCW060310K0FKEI")
      )
      (libsource (lib "Schematic-Lib-PhilsLab") (part "CRCW060310K0FKEI"))
    )
    (comp (ref "R49")
      (value "10k 1/8W")
      (footprint "RES_0603")
      (description "Thick Film Resistors - SMD 10K OHM 1%")
      (fields
        (field (name "MANUFACTURER") "Vishay")
        (field (name "MANUFACTURER PART NUMBER") "CRCW060310K0FKEI")
      )
      (libsource (lib "Schematic-Lib-PhilsLab") (part "CRCW060310K0FKEI"))
    )
    (comp (ref "RDRV1")
      (value "39 3/4W 1%")
      (footprint "RES_0603")
      (description "Thick Film Resistors - SMD 0.75W 39ohms 1% High Power AEC-Q200")
      (fields
        (field (name "MANUFACTURER") "Vishay")
        (field (name "MANUFACTURER PART NUMBER") "CRCW060339R0FKEAHP")
      )
      (libsource (lib "Schematic-Lib-PhilsLab") (part "CRCW060339R0FKEAHP"))
    )
    (comp (ref "RDRV2")
      (value "39 3/4W 1%")
      (footprint "RES_0603")
      (description "Thick Film Resistors - SMD 0.75W 39ohms 1% High Power AEC-Q200")
      (fields
        (field (name "MANUFACTURER") "Vishay")
        (field (name "MANUFACTURER PART NUMBER") "CRCW060339R0FKEAHP")
      )
      (libsource (lib "Schematic-Lib-PhilsLab") (part "CRCW060339R0FKEAHP"))
    )
    (comp (ref "RDRV3")
      (value "39 3/4W 1%")
      (footprint "RES_0603")
      (description "Thick Film Resistors - SMD 0.75W 39ohms 1% High Power AEC-Q200")
      (fields
        (field (name "MANUFACTURER") "Vishay")
        (field (name "MANUFACTURER PART NUMBER") "CRCW060339R0FKEAHP")
      )
      (libsource (lib "Schematic-Lib-PhilsLab") (part "CRCW060339R0FKEAHP"))
    )
    (comp (ref "RDRV4")
      (value "39 3/4W 1%")
      (footprint "RES_0603")
      (description "Thick Film Resistors - SMD 0.75W 39ohms 1% High Power AEC-Q200")
      (fields
        (field (name "MANUFACTURER") "Vishay")
        (field (name "MANUFACTURER PART NUMBER") "CRCW060339R0FKEAHP")
      )
      (libsource (lib "Schematic-Lib-PhilsLab") (part "CRCW060339R0FKEAHP"))
    )
    (comp (ref "RDRV5")
      (value "39 3/4W 1%")
      (footprint "RES_0603")
      (description "Thick Film Resistors - SMD 0.75W 39ohms 1% High Power AEC-Q200")
      (fields
        (field (name "MANUFACTURER") "Vishay")
        (field (name "MANUFACTURER PART NUMBER") "CRCW060339R0FKEAHP")
      )
      (libsource (lib "Schematic-Lib-PhilsLab") (part "CRCW060339R0FKEAHP"))
    )
    (comp (ref "RDRV6")
      (value "39 3/4W 1%")
      (footprint "RES_0603")
      (description "Thick Film Resistors - SMD 0.75W 39ohms 1% High Power AEC-Q200")
      (fields
        (field (name "MANUFACTURER") "Vishay")
        (field (name "MANUFACTURER PART NUMBER") "CRCW060339R0FKEAHP")
      )
      (libsource (lib "Schematic-Lib-PhilsLab") (part "CRCW060339R0FKEAHP"))
    )
    (comp (ref "RDRV7")
      (value "39 3/4W 1%")
      (footprint "RES_0603")
      (description "Thick Film Resistors - SMD 0.75W 39ohms 1% High Power AEC-Q200")
      (fields
        (field (name "MANUFACTURER") "Vishay")
        (field (name "MANUFACTURER PART NUMBER") "CRCW060339R0FKEAHP")
      )
      (libsource (lib "Schematic-Lib-PhilsLab") (part "CRCW060339R0FKEAHP"))
    )
    (comp (ref "RDRV8")
      (value "39 3/4W 1%")
      (footprint "RES_0603")
      (description "Thick Film Resistors - SMD 0.75W 39ohms 1% High Power AEC-Q200")
      (fields
        (field (name "MANUFACTURER") "Vishay")
        (field (name "MANUFACTURER PART NUMBER") "CRCW060339R0FKEAHP")
      )
      (libsource (lib "Schematic-Lib-PhilsLab") (part "CRCW060339R0FKEAHP"))
    )
    (comp (ref "RDRV9")
      (value "39 3/4W 1%")
      (footprint "RES_0603")
      (description "Thick Film Resistors - SMD 0.75W 39ohms 1% High Power AEC-Q200")
      (fields
        (field (name "MANUFACTURER") "Vishay")
        (field (name "MANUFACTURER PART NUMBER") "CRCW060339R0FKEAHP")
      )
      (libsource (lib "Schematic-Lib-PhilsLab") (part "CRCW060339R0FKEAHP"))
    )
    (comp (ref "RDRV10")
      (value "39 3/4W 1%")
      (footprint "RES_0603")
      (description "Thick Film Resistors - SMD 0.75W 39ohms 1% High Power AEC-Q200")
      (fields
        (field (name "MANUFACTURER") "Vishay")
        (field (name "MANUFACTURER PART NUMBER") "CRCW060339R0FKEAHP")
      )
      (libsource (lib "Schematic-Lib-PhilsLab") (part "CRCW060339R0FKEAHP"))
    )
    (comp (ref "RDRV11")
      (value "39 3/4W 1%")
      (footprint "RES_0603")
      (description "Thick Film Resistors - SMD 0.75W 39ohms 1% High Power AEC-Q200")
      (fields
        (field (name "MANUFACTURER") "Vishay")
        (field (name "MANUFACTURER PART NUMBER") "CRCW060339R0FKEAHP")
      )
      (libsource (lib "Schematic-Lib-PhilsLab") (part "CRCW060339R0FKEAHP"))
    )
    (comp (ref "RDRV12")
      (value "39 3/4W 1%")
      (footprint "RES_0603")
      (description "Thick Film Resistors - SMD 0.75W 39ohms 1% High Power AEC-Q200")
      (fields
        (field (name "MANUFACTURER") "Vishay")
        (field (name "MANUFACTURER PART NUMBER") "CRCW060339R0FKEAHP")
      )
      (libsource (lib "Schematic-Lib-PhilsLab") (part "CRCW060339R0FKEAHP"))
    )
    (comp (ref "RDRV13")
      (value "39 3/4W 1%")
      (footprint "RES_0603")
      (description "Thick Film Resistors - SMD 0.75W 39ohms 1% High Power AEC-Q200")
      (fields
        (field (name "MANUFACTURER") "Vishay")
        (field (name "MANUFACTURER PART NUMBER") "CRCW060339R0FKEAHP")
      )
      (libsource (lib "Schematic-Lib-PhilsLab") (part "CRCW060339R0FKEAHP"))
    )
    (comp (ref "RDRV14")
      (value "39 3/4W 1%")
      (footprint "RES_0603")
      (description "Thick Film Resistors - SMD 0.75W 39ohms 1% High Power AEC-Q200")
      (fields
        (field (name "MANUFACTURER") "Vishay")
        (field (name "MANUFACTURER PART NUMBER") "CRCW060339R0FKEAHP")
      )
      (libsource (lib "Schematic-Lib-PhilsLab") (part "CRCW060339R0FKEAHP"))
    )
    (comp (ref "RISENSE1")
      (value "0k1 1W 1%")
      (footprint "RES_2010")
      (description "Current Sense Resistors - SMD CHIP RESISTOR Low Value 100ohm 1W 1% 2010 Thick Film Resistor")
      (fields
        (field (name "MANUFACTURER") "Bourns")
        (field (name "MANUFACTURER PART NUMBER") "CRM2010-FX-1000ELF")
      )
      (libsource (lib "Schematic-Lib-PhilsLab") (part "CRM2010-FX-1000ELF"))
    )
    (comp (ref "RISENSE2")
      (value "0k1 1W 1%")
      (footprint "RES_2010")
      (description "Current Sense Resistors - SMD CHIP RESISTOR Low Value 100ohm 1W 1% 2010 Thick Film Resistor")
      (fields
        (field (name "MANUFACTURER") "Bourns")
        (field (name "MANUFACTURER PART NUMBER") "CRM2010-FX-1000ELF")
      )
      (libsource (lib "Schematic-Lib-PhilsLab") (part "CRM2010-FX-1000ELF"))
    )
    (comp (ref "RLPF1")
      (value "0k1 1/10W 5%")
      (footprint "RES_0603")
      (description "Thick Film Resistors - SMD 1/10Watt 100ohms 5% 0603 Commercial Use")
      (fields
        (field (name "MANUFACTURER") "Vishay")
        (field (name "MANUFACTURER PART NUMBER") "CRCW0603100RJNEBC")
      )
      (libsource (lib "Schematic-Lib-PhilsLab") (part "CRCW0603100RJNEBC"))
    )
    (comp (ref "RLPF2")
      (value "0k1 1/10W 5%")
      (footprint "RES_0603")
      (description "Thick Film Resistors - SMD 1/10Watt 100ohms 5% 0603 Commercial Use")
      (fields
        (field (name "MANUFACTURER") "Vishay")
        (field (name "MANUFACTURER PART NUMBER") "CRCW0603100RJNEBC")
      )
      (libsource (lib "Schematic-Lib-PhilsLab") (part "CRCW0603100RJNEBC"))
    )
    (comp (ref "RLPF3")
      (value "0k1 1/10W 5%")
      (footprint "RES_0603")
      (description "Thick Film Resistors - SMD 1/10Watt 100ohms 5% 0603 Commercial Use")
      (fields
        (field (name "MANUFACTURER") "Vishay")
        (field (name "MANUFACTURER PART NUMBER") "CRCW0603100RJNEBC")
      )
      (libsource (lib "Schematic-Lib-PhilsLab") (part "CRCW0603100RJNEBC"))
    )
    (comp (ref "RLPF4")
      (value "0k1 1/10W 5%")
      (footprint "RES_0603")
      (description "Thick Film Resistors - SMD 1/10Watt 100ohms 5% 0603 Commercial Use")
      (fields
        (field (name "MANUFACTURER") "Vishay")
        (field (name "MANUFACTURER PART NUMBER") "CRCW0603100RJNEBC")
      )
      (libsource (lib "Schematic-Lib-PhilsLab") (part "CRCW0603100RJNEBC"))
    )
    (comp (ref "RLPF5")
      (value "0k1 1/10W 5%")
      (footprint "RES_0603")
      (description "Thick Film Resistors - SMD 1/10Watt 100ohms 5% 0603 Commercial Use")
      (fields
        (field (name "MANUFACTURER") "Vishay")
        (field (name "MANUFACTURER PART NUMBER") "CRCW0603100RJNEBC")
      )
      (libsource (lib "Schematic-Lib-PhilsLab") (part "CRCW0603100RJNEBC"))
    )
    (comp (ref "RLPF6")
      (value "0k1 1/10W 5%")
      (footprint "RES_0603")
      (description "Thick Film Resistors - SMD 1/10Watt 100ohms 5% 0603 Commercial Use")
      (fields
        (field (name "MANUFACTURER") "Vishay")
        (field (name "MANUFACTURER PART NUMBER") "CRCW0603100RJNEBC")
      )
      (libsource (lib "Schematic-Lib-PhilsLab") (part "CRCW0603100RJNEBC"))
    )
    (comp (ref "RLPF7")
      (value "0k1 1/10W 5%")
      (footprint "RES_0603")
      (description "Thick Film Resistors - SMD 1/10Watt 100ohms 5% 0603 Commercial Use")
      (fields
        (field (name "MANUFACTURER") "Vishay")
        (field (name "MANUFACTURER PART NUMBER") "CRCW0603100RJNEBC")
      )
      (libsource (lib "Schematic-Lib-PhilsLab") (part "CRCW0603100RJNEBC"))
    )
    (comp (ref "RLPF8")
      (value "0k1 1/10W 5%")
      (footprint "RES_0603")
      (description "Thick Film Resistors - SMD 1/10Watt 100ohms 5% 0603 Commercial Use")
      (fields
        (field (name "MANUFACTURER") "Vishay")
        (field (name "MANUFACTURER PART NUMBER") "CRCW0603100RJNEBC")
      )
      (libsource (lib "Schematic-Lib-PhilsLab") (part "CRCW0603100RJNEBC"))
    )
    (comp (ref "RLPF9")
      (value "0k1 1/10W 5%")
      (footprint "RES_0603")
      (description "Thick Film Resistors - SMD 1/10Watt 100ohms 5% 0603 Commercial Use")
      (fields
        (field (name "MANUFACTURER") "Vishay")
        (field (name "MANUFACTURER PART NUMBER") "CRCW0603100RJNEBC")
      )
      (libsource (lib "Schematic-Lib-PhilsLab") (part "CRCW0603100RJNEBC"))
    )
    (comp (ref "RLPF10")
      (value "0k1 1/10W 5%")
      (footprint "RES_0603")
      (description "Thick Film Resistors - SMD 1/10Watt 100ohms 5% 0603 Commercial Use")
      (fields
        (field (name "MANUFACTURER") "Vishay")
        (field (name "MANUFACTURER PART NUMBER") "CRCW0603100RJNEBC")
      )
      (libsource (lib "Schematic-Lib-PhilsLab") (part "CRCW0603100RJNEBC"))
    )
    (comp (ref "RLPF11")
      (value "0k1 1/10W 5%")
      (footprint "RES_0603")
      (description "Thick Film Resistors - SMD 1/10Watt 100ohms 5% 0603 Commercial Use")
      (fields
        (field (name "MANUFACTURER") "Vishay")
        (field (name "MANUFACTURER PART NUMBER") "CRCW0603100RJNEBC")
      )
      (libsource (lib "Schematic-Lib-PhilsLab") (part "CRCW0603100RJNEBC"))
    )
    (comp (ref "RLPF12")
      (value "0k1 1/10W 5%")
      (footprint "RES_0603")
      (description "Thick Film Resistors - SMD 1/10Watt 100ohms 5% 0603 Commercial Use")
      (fields
        (field (name "MANUFACTURER") "Vishay")
        (field (name "MANUFACTURER PART NUMBER") "CRCW0603100RJNEBC")
      )
      (libsource (lib "Schematic-Lib-PhilsLab") (part "CRCW0603100RJNEBC"))
    )
    (comp (ref "RLPF13")
      (value "0k1 1/10W 5%")
      (footprint "RES_0603")
      (description "Thick Film Resistors - SMD 1/10Watt 100ohms 5% 0603 Commercial Use")
      (fields
        (field (name "MANUFACTURER") "Vishay")
        (field (name "MANUFACTURER PART NUMBER") "CRCW0603100RJNEBC")
      )
      (libsource (lib "Schematic-Lib-PhilsLab") (part "CRCW0603100RJNEBC"))
    )
    (comp (ref "RLPF14")
      (value "0k1 1/10W 5%")
      (footprint "RES_0603")
      (description "Thick Film Resistors - SMD 1/10Watt 100ohms 5% 0603 Commercial Use")
      (fields
        (field (name "MANUFACTURER") "Vishay")
        (field (name "MANUFACTURER PART NUMBER") "CRCW0603100RJNEBC")
      )
      (libsource (lib "Schematic-Lib-PhilsLab") (part "CRCW0603100RJNEBC"))
    )
    (comp (ref "RLPF15")
      (value "0k1 1/10W 5%")
      (footprint "RES_0603")
      (description "Thick Film Resistors - SMD 1/10Watt 100ohms 5% 0603 Commercial Use")
      (fields
        (field (name "MANUFACTURER") "Vishay")
        (field (name "MANUFACTURER PART NUMBER") "CRCW0603100RJNEBC")
      )
      (libsource (lib "Schematic-Lib-PhilsLab") (part "CRCW0603100RJNEBC"))
    )
    (comp (ref "RSENSE")
      (value "100u 15W 1%")
      (footprint "RES_5931")
      (description "Current Sense Resistors - SMD 0.0001 ohm 1%")
      (fields
        (field (name "MANUFACTURER") "Vishay/Dale")
        (field (name "MANUFACTURER PART NUMBER") "WSLP5931L1000FEA")
      )
      (libsource (lib "Schematic-Lib-PhilsLab") (part "WSLP5931L1000FEA"))
    )
    (comp (ref "TPC0")
      (value "5014")
      (footprint "KSTN-5014_V")
      (description "Test Point, Yellow, Through Hole, RoHS, Bulk")
      (fields (field (name "MANUFACTURER") "Keystone"))
      (libsource (lib "Altium Content Vault") (part "TESTPOINT_YELLOW"))
    )
    (comp (ref "TPC1")
      (value "5014")
      (footprint "KSTN-5014_V")
      (description "Test Point, Yellow, Through Hole, RoHS, Bulk")
      (fields (field (name "MANUFACTURER") "Keystone"))
      (libsource (lib "Altium Content Vault") (part "TESTPOINT_YELLOW"))
    )
    (comp (ref "TPC2")
      (value "5014")
      (footprint "KSTN-5014_V")
      (description "Test Point, Yellow, Through Hole, RoHS, Bulk")
      (fields (field (name "MANUFACTURER") "Keystone"))
      (libsource (lib "Altium Content Vault") (part "TESTPOINT_YELLOW"))
    )
    (comp (ref "TPC3")
      (value "5014")
      (footprint "KSTN-5014_V")
      (description "Test Point, Yellow, Through Hole, RoHS, Bulk")
      (fields (field (name "MANUFACTURER") "Keystone"))
      (libsource (lib "Altium Content Vault") (part "TESTPOINT_YELLOW"))
    )
    (comp (ref "TPC4")
      (value "5014")
      (footprint "KSTN-5014_V")
      (description "Test Point, Yellow, Through Hole, RoHS, Bulk")
      (fields (field (name "MANUFACTURER") "Keystone"))
      (libsource (lib "Altium Content Vault") (part "TESTPOINT_YELLOW"))
    )
    (comp (ref "TPC5")
      (value "5014")
      (footprint "KSTN-5014_V")
      (description "Test Point, Yellow, Through Hole, RoHS, Bulk")
      (fields (field (name "MANUFACTURER") "Keystone"))
      (libsource (lib "Altium Content Vault") (part "TESTPOINT_YELLOW"))
    )
    (comp (ref "TPC6")
      (value "5014")
      (footprint "KSTN-5014_V")
      (description "Test Point, Yellow, Through Hole, RoHS, Bulk")
      (fields (field (name "MANUFACTURER") "Keystone"))
      (libsource (lib "Altium Content Vault") (part "TESTPOINT_YELLOW"))
    )
    (comp (ref "TPC7")
      (value "5014")
      (footprint "KSTN-5014_V")
      (description "Test Point, Yellow, Through Hole, RoHS, Bulk")
      (fields (field (name "MANUFACTURER") "Keystone"))
      (libsource (lib "Altium Content Vault") (part "TESTPOINT_YELLOW"))
    )
    (comp (ref "TPC8")
      (value "5014")
      (footprint "KSTN-5014_V")
      (description "Test Point, Yellow, Through Hole, RoHS, Bulk")
      (fields (field (name "MANUFACTURER") "Keystone"))
      (libsource (lib "Altium Content Vault") (part "TESTPOINT_YELLOW"))
    )
    (comp (ref "TPC9")
      (value "5014")
      (footprint "KSTN-5014_V")
      (description "Test Point, Yellow, Through Hole, RoHS, Bulk")
      (fields (field (name "MANUFACTURER") "Keystone"))
      (libsource (lib "Altium Content Vault") (part "TESTPOINT_YELLOW"))
    )
    (comp (ref "TPC10")
      (value "5014")
      (footprint "KSTN-5014_V")
      (description "Test Point, Yellow, Through Hole, RoHS, Bulk")
      (fields (field (name "MANUFACTURER") "Keystone"))
      (libsource (lib "Altium Content Vault") (part "TESTPOINT_YELLOW"))
    )
    (comp (ref "TPC11")
      (value "5014")
      (footprint "KSTN-5014_V")
      (description "Test Point, Yellow, Through Hole, RoHS, Bulk")
      (fields (field (name "MANUFACTURER") "Keystone"))
      (libsource (lib "Altium Content Vault") (part "TESTPOINT_YELLOW"))
    )
    (comp (ref "TPC12")
      (value "5014")
      (footprint "KSTN-5014_V")
      (description "Test Point, Yellow, Through Hole, RoHS, Bulk")
      (fields (field (name "MANUFACTURER") "Keystone"))
      (libsource (lib "Altium Content Vault") (part "TESTPOINT_YELLOW"))
    )
    (comp (ref "TPC13")
      (value "5014")
      (footprint "KSTN-5014_V")
      (description "Test Point, Yellow, Through Hole, RoHS, Bulk")
      (fields (field (name "MANUFACTURER") "Keystone"))
      (libsource (lib "Altium Content Vault") (part "TESTPOINT_YELLOW"))
    )
    (comp (ref "TPC14")
      (value "5014")
      (footprint "KSTN-5014_V")
      (description "Test Point, Yellow, Through Hole, RoHS, Bulk")
      (fields (field (name "MANUFACTURER") "Keystone"))
      (libsource (lib "Altium Content Vault") (part "TESTPOINT_YELLOW"))
    )
    (comp (ref "TPVBAT")
      (value "5014")
      (footprint "KSTN-5014_V")
      (description "Test Point, Yellow, Through Hole, RoHS, Bulk")
      (fields (field (name "MANUFACTURER") "Keystone"))
      (libsource (lib "Altium Content Vault") (part "TESTPOINT_YELLOW"))
    )
    (comp (ref "TPVREG")
      (value "5014")
      (footprint "KSTN-5014_V")
      (description "Test Point, Yellow, Through Hole, RoHS, Bulk")
      (fields (field (name "MANUFACTURER") "Keystone"))
      (libsource (lib "Altium Content Vault") (part "TESTPOINT_YELLOW"))
    )
    (comp (ref "U5")
      (value "L9963E-TR")
      (footprint "L9963E-TR")
      (libsource (lib "Schematic-Lib-PhilsLab") (part "L9963E-TR"))
    )
  )
  (nets
    (net (code "1") (name "+3V3") (class "Default")
      (node (ref "C39") (pin "2") (pinfunction "2_2") (pintype "passive"))
      (node (ref "C40") (pin "2") (pinfunction "2_2") (pintype "passive"))
      (node (ref "C41") (pin "2") (pinfunction "2_2") (pintype "passive"))
      (node (ref "C42") (pin "2") (pinfunction "2_2") (pintype "passive"))
      (node (ref "J8") (pin "1") (pinfunction "1_1") (pintype "passive"))
      (node (ref "Q3") (pin "1") (pinfunction "G_1") (pintype "passive"))
      (node (ref "Q6") (pin "1") (pinfunction "G_1") (pintype "passive"))
      (node (ref "Q7") (pin "1") (pinfunction "G_1") (pintype "passive"))
      (node (ref "R12") (pin "2") (pinfunction "2_2") (pintype "passive"))
      (node (ref "R18") (pin "2") (pinfunction "2_2") (pintype "passive"))
      (node (ref "R19") (pin "2") (pinfunction "2_2") (pintype "passive"))
      (node (ref "R28") (pin "2") (pinfunction "2_2") (pintype "passive"))
      (node (ref "R29") (pin "2") (pinfunction "2_2") (pintype "passive"))
      (node (ref "R30") (pin "2") (pinfunction "2_2") (pintype "passive"))
      (node (ref "R31") (pin "2") (pinfunction "2_2") (pintype "passive"))
      (node (ref "R39") (pin "2") (pinfunction "2_2") (pintype "passive"))
    )
    (net (code "2") (name "+5V") (class "Default")
      (node (ref "CVCOM") (pin "2") (pinfunction "2_2") (pintype "passive"))
      (node (ref "R10") (pin "2") (pinfunction "2_2") (pintype "passive"))
      (node (ref "R17") (pin "2") (pinfunction "2_2") (pintype "passive"))
      (node (ref "R37") (pin "2") (pinfunction "2_2") (pintype "passive"))
      (node (ref "U5") (pin "20") (pinfunction "SPIEN_20") (pintype "input"))
      (node (ref "U5") (pin "5") (pinfunction "VCOM_5") (pintype "power_in"))
    )
    (net (code "3") (name "/C0") (class "Default")
      (node (ref "CESD16") (pin "2") (pinfunction "2_2") (pintype "passive"))
      (node (ref "CESD17") (pin "1") (pinfunction "1_1") (pintype "passive"))
      (node (ref "FBSNS15") (pin "1") (pinfunction "1_1") (pintype "passive"))
      (node (ref "J7") (pin "16") (pinfunction "16_16") (pintype "passive"))
      (node (ref "RISENSE2") (pin "2") (pinfunction "2_2") (pintype "passive"))
      (node (ref "RSENSE") (pin "1") (pinfunction "1_1") (pintype "passive"))
    )
    (net (code "4") (name "/C1") (class "Default")
      (node (ref "CESD15") (pin "1") (pinfunction "1_1") (pintype "passive"))
      (node (ref "FBSNS14") (pin "1") (pinfunction "1_1") (pintype "passive"))
      (node (ref "J7") (pin "15") (pinfunction "15_15") (pintype "passive"))
    )
    (net (code "5") (name "/C2") (class "Default")
      (node (ref "CESD13") (pin "1") (pinfunction "1_1") (pintype "passive"))
      (node (ref "FBSNS13") (pin "1") (pinfunction "1_1") (pintype "passive"))
      (node (ref "J7") (pin "14") (pinfunction "14_14") (pintype "passive"))
    )
    (net (code "6") (name "/C3") (class "Default")
      (node (ref "CESD12") (pin "1") (pinfunction "1_1") (pintype "passive"))
      (node (ref "FBSNS12") (pin "1") (pinfunction "1_1") (pintype "passive"))
      (node (ref "J7") (pin "13") (pinfunction "13_13") (pintype "passive"))
    )
    (net (code "7") (name "/C4") (class "Default")
      (node (ref "CESD11") (pin "1") (pinfunction "1_1") (pintype "passive"))
      (node (ref "FBSNS11") (pin "1") (pinfunction "1_1") (pintype "passive"))
      (node (ref "J7") (pin "12") (pinfunction "12_12") (pintype "passive"))
    )
    (net (code "8") (name "/C5") (class "Default")
      (node (ref "CESD10") (pin "1") (pinfunction "1_1") (pintype "passive"))
      (node (ref "FBSNS10") (pin "1") (pinfunction "1_1") (pintype "passive"))
      (node (ref "J7") (pin "11") (pinfunction "11_11") (pintype "passive"))
    )
    (net (code "9") (name "/C6") (class "Default")
      (node (ref "CESD9") (pin "1") (pinfunction "1_1") (pintype "passive"))
      (node (ref "FBSNS9") (pin "1") (pinfunction "1_1") (pintype "passive"))
      (node (ref "J7") (pin "10") (pinfunction "10_10") (pintype "passive"))
    )
    (net (code "10") (name "/C7") (class "Default")
      (node (ref "CESD8") (pin "1") (pinfunction "1_1") (pintype "passive"))
      (node (ref "FBSNS8") (pin "1") (pinfunction "1_1") (pintype "passive"))
      (node (ref "J7") (pin "9") (pinfunction "9_9") (pintype "passive"))
    )
    (net (code "11") (name "/C8") (class "Default")
      (node (ref "CESD7") (pin "1") (pinfunction "1_1") (pintype "passive"))
      (node (ref "FBSNS7") (pin "1") (pinfunction "1_1") (pintype "passive"))
      (node (ref "J7") (pin "8") (pinfunction "8_8") (pintype "passive"))
    )
    (net (code "12") (name "/C9") (class "Default")
      (node (ref "CESD6") (pin "1") (pinfunction "1_1") (pintype "passive"))
      (node (ref "FBSNS6") (pin "1") (pinfunction "1_1") (pintype "passive"))
      (node (ref "J7") (pin "7") (pinfunction "7_7") (pintype "passive"))
    )
    (net (code "13") (name "/C10") (class "Default")
      (node (ref "CESD5") (pin "1") (pinfunction "1_1") (pintype "passive"))
      (node (ref "FBSNS5") (pin "1") (pinfunction "1_1") (pintype "passive"))
      (node (ref "J7") (pin "6") (pinfunction "6_6") (pintype "passive"))
    )
    (net (code "14") (name "/C11") (class "Default")
      (node (ref "CESD4") (pin "1") (pinfunction "1_1") (pintype "passive"))
      (node (ref "FBSNS4") (pin "1") (pinfunction "1_1") (pintype "passive"))
      (node (ref "J7") (pin "5") (pinfunction "5_5") (pintype "passive"))
    )
    (net (code "15") (name "/C12") (class "Default")
      (node (ref "CESD3") (pin "1") (pinfunction "1_1") (pintype "passive"))
      (node (ref "FBSNS3") (pin "1") (pinfunction "1_1") (pintype "passive"))
      (node (ref "J7") (pin "4") (pinfunction "4_4") (pintype "passive"))
    )
    (net (code "16") (name "/C13") (class "Default")
      (node (ref "CESD2") (pin "1") (pinfunction "1_1") (pintype "passive"))
      (node (ref "FBSNS2") (pin "1") (pinfunction "1_1") (pintype "passive"))
      (node (ref "J7") (pin "3") (pinfunction "3_3") (pintype "passive"))
    )
    (net (code "17") (name "/C14") (class "Default")
      (node (ref "CESD1") (pin "1") (pinfunction "1_1") (pintype "passive"))
      (node (ref "FBSNS1") (pin "1") (pinfunction "1_1") (pintype "passive"))
      (node (ref "J7") (pin "2") (pinfunction "2_2") (pintype "passive"))
    )
    (net (code "18") (name "/CAP1") (class "Default")
      (node (ref "C37") (pin "1") (pinfunction "1_1") (pintype "passive"))
      (node (ref "U5") (pin "64") (pinfunction "CAP1_64") (pintype "input"))
    )
    (net (code "19") (name "/CAP2") (class "Default")
      (node (ref "C37") (pin "2") (pinfunction "2_2") (pintype "passive"))
      (node (ref "U5") (pin "63") (pinfunction "CAP2_63") (pintype "input"))
    )
    (net (code "20") (name "/FAULTH_L9963") (class "Default")
      (node (ref "Q6") (pin "2") (pinfunction "S_2") (pintype "passive"))
      (node (ref "R17") (pin "1") (pinfunction "1_1") (pintype "passive"))
      (node (ref "R25") (pin "2") (pinfunction "2_2") (pintype "passive"))
    )
    (net (code "21") (name "/FAULTH_L_MCU") (class "Default")
      (node (ref "Q6") (pin "3") (pinfunction "D_3") (pintype "passive"))
      (node (ref "R18") (pin "1") (pinfunction "1_1") (pintype "passive"))
    )
    (net (code "22") (name "/FAULTL_L9963") (class "Default")
      (node (ref "Q7") (pin "2") (pinfunction "S_2") (pintype "passive"))
      (node (ref "R27") (pin "2") (pinfunction "2_2") (pintype "passive"))
      (node (ref "R37") (pin "1") (pinfunction "1_1") (pintype "passive"))
      (node (ref "U5") (pin "11") (pinfunction "GPIO2_FAULTL_11") (pintype "output"))
    )
    (net (code "23") (name "/FAULTL_L_MCU") (class "Default")
      (node (ref "Q7") (pin "3") (pinfunction "D_3") (pintype "passive"))
      (node (ref "R39") (pin "1") (pinfunction "1_1") (pintype "passive"))
    )
    (net (code "24") (name "/GPIO1_FAULTH") (class "Default")
      (node (ref "C38") (pin "2") (pinfunction "2_2") (pintype "passive"))
      (node (ref "D8") (pin "1") (pinfunction "K_1") (pintype "passive"))
      (node (ref "R25") (pin "1") (pinfunction "1_1") (pintype "passive"))
      (node (ref "R26") (pin "2") (pinfunction "2_2") (pintype "passive"))
      (node (ref "U5") (pin "10") (pinfunction "GPIO1_FAULTH_10") (pintype "input"))
    )
    (net (code "25") (name "/GPIO9_MISO") (class "Default")
      (node (ref "Q3") (pin "2") (pinfunction "S_2") (pintype "passive"))
      (node (ref "R10") (pin "1") (pinfunction "1_1") (pintype "passive"))
      (node (ref "U5") (pin "2") (pinfunction "GPIO9_SDO_2") (pintype "bidirectional"))
    )
    (net (code "26") (name "/ISENSEM") (class "Default")
      (node (ref "CESD14") (pin "2") (pinfunction "2_2") (pintype "passive"))
      (node (ref "J7") (pin "20") (pinfunction "20_20") (pintype "passive"))
      (node (ref "Q5") (pin "3") (pinfunction "S_3") (pintype "passive"))
      (node (ref "R49") (pin "1") (pinfunction "1_1") (pintype "passive"))
      (node (ref "RISENSE1") (pin "2") (pinfunction "2_2") (pintype "passive"))
      (node (ref "RSENSE") (pin "2") (pinfunction "2_2") (pintype "passive"))
    )
    (net (code "27") (name "/ISENSEM_IO") (class "Default")
      (node (ref "CISENSE_1") (pin "2") (pinfunction "2_2") (pintype "passive"))
      (node (ref "CISENSE_2") (pin "2") (pinfunction "2_2") (pintype "passive"))
      (node (ref "CISENSE_3") (pin "2") (pinfunction "2_2") (pintype "passive"))
      (node (ref "RISENSE1") (pin "1") (pinfunction "1_1") (pintype "passive"))
      (node (ref "U5") (pin "24") (pinfunction "ISENSEm_24") (pintype "input"))
    )
    (net (code "28") (name "/ISENSEP_IO") (class "Default")
      (node (ref "CISENSE_1") (pin "1") (pinfunction "1_1") (pintype "passive"))
      (node (ref "CISENSE_2") (pin "1") (pinfunction "1_1") (pintype "passive"))
      (node (ref "CISENSE_3") (pin "1") (pinfunction "1_1") (pintype "passive"))
      (node (ref "RISENSE2") (pin "1") (pinfunction "1_1") (pintype "passive"))
      (node (ref "U5") (pin "23") (pinfunction "ISENSEp_23") (pintype "input"))
    )
    (net (code "29") (name "/MHOT_GATE") (class "Default")
      (node (ref "C36") (pin "2") (pinfunction "2_2") (pintype "passive"))
      (node (ref "MHOT") (pin "4") (pinfunction "G_4") (pintype "input"))
      (node (ref "R22") (pin "2") (pinfunction "2_2") (pintype "passive"))
    )
    (net (code "30") (name "/MHOT_VGS") (class "Default")
      (node (ref "J8") (pin "2") (pinfunction "2_2") (pintype "passive"))
      (node (ref "R22") (pin "1") (pinfunction "1_1") (pintype "passive"))
      (node (ref "R24") (pin "2") (pinfunction "2_2") (pintype "passive"))
    )
    (net (code "31") (name "/NPNDRV") (class "Default")
      (node (ref "C32") (pin "2") (pinfunction "2_2") (pintype "passive"))
      (node (ref "C33") (pin "2") (pinfunction "2_2") (pintype "passive"))
      (node (ref "C34") (pin "2") (pinfunction "2_2") (pintype "passive"))
      (node (ref "D7") (pin "K") (pinfunction "K_K") (pintype "passive"))
      (node (ref "FB1") (pin "2") (pinfunction "2_2") (pintype "passive"))
      (node (ref "Q2") (pin "4") (pinfunction "G_4") (pintype "passive"))
      (node (ref "Q2") (pin "5-6-7-8") (pinfunction "D_5-6-7-8") (pintype "passive"))
      (node (ref "TPVBAT") (pin "1") (pinfunction "1_1") (pintype "passive"))
      (node (ref "U5") (pin "17") (pinfunction "NPNDRV_17") (pintype "output"))
      (node (ref "U5") (pin "62") (pinfunction "VBAT_62") (pintype "power_in"))
    )
    (net (code "32") (name "/NTC1+") (class "Default")
      (node (ref "C39") (pin "1") (pinfunction "1_1") (pintype "passive"))
      (node (ref "C46") (pin "2") (pinfunction "2_2") (pintype "passive"))
      (node (ref "C47") (pin "2") (pinfunction "2_2") (pintype "passive"))
      (node (ref "J7") (pin "21") (pinfunction "21_21") (pintype "passive"))
      (node (ref "R28") (pin "1") (pinfunction "1_1") (pintype "passive"))
      (node (ref "R32") (pin "2") (pinfunction "2_2") (pintype "passive"))
    )
    (net (code "33") (name "/NTC1+_IO") (class "Default")
      (node (ref "R32") (pin "1") (pinfunction "1_1") (pintype "passive"))
      (node (ref "U5") (pin "12") (pinfunction "GPIO3_12") (pintype "bidirectional"))
    )
    (net (code "34") (name "/NTC2+") (class "Default")
      (node (ref "C40") (pin "1") (pinfunction "1_1") (pintype "passive"))
      (node (ref "C45") (pin "2") (pinfunction "2_2") (pintype "passive"))
      (node (ref "C50") (pin "2") (pinfunction "2_2") (pintype "passive"))
      (node (ref "J7") (pin "23") (pinfunction "23_23") (pintype "passive"))
      (node (ref "R30") (pin "1") (pinfunction "1_1") (pintype "passive"))
      (node (ref "R33") (pin "2") (pinfunction "2_2") (pintype "passive"))
    )
    (net (code "35") (name "/NTC2+_IO") (class "Default")
      (node (ref "R33") (pin "1") (pinfunction "1_1") (pintype "passive"))
      (node (ref "U5") (pin "13") (pinfunction "GPIO4_13") (pintype "bidirectional"))
    )
    (net (code "36") (name "/NTC3+") (class "Default")
      (node (ref "C41") (pin "1") (pinfunction "1_1") (pintype "passive"))
      (node (ref "C44") (pin "2") (pinfunction "2_2") (pintype "passive"))
      (node (ref "C49") (pin "2") (pinfunction "2_2") (pintype "passive"))
      (node (ref "J7") (pin "25") (pinfunction "25_25") (pintype "passive"))
      (node (ref "R29") (pin "1") (pinfunction "1_1") (pintype "passive"))
      (node (ref "R34") (pin "2") (pinfunction "2_2") (pintype "passive"))
    )
    (net (code "37") (name "/NTC3+_IO") (class "Default")
      (node (ref "R34") (pin "1") (pinfunction "1_1") (pintype "passive"))
      (node (ref "U5") (pin "14") (pinfunction "GPIO5_14") (pintype "bidirectional"))
    )
    (net (code "38") (name "/NTC4+") (class "Default")
      (node (ref "C42") (pin "1") (pinfunction "1_1") (pintype "passive"))
      (node (ref "C43") (pin "2") (pinfunction "2_2") (pintype "passive"))
      (node (ref "C48") (pin "2") (pinfunction "2_2") (pintype "passive"))
      (node (ref "J7") (pin "27") (pinfunction "27_27") (pintype "passive"))
      (node (ref "R31") (pin "1") (pinfunction "1_1") (pintype "passive"))
      (node (ref "R35") (pin "2") (pinfunction "2_2") (pintype "passive"))
    )
    (net (code "39") (name "/NTC4+_IO") (class "Default")
      (node (ref "R35") (pin "1") (pinfunction "1_1") (pintype "passive"))
      (node (ref "U5") (pin "15") (pinfunction "GPIO6_15") (pintype "bidirectional"))
    )
    (net (code "40") (name "/NTC_INTERNAL_INPUT") (class "Default")
      (node (ref "C31") (pin "2") (pinfunction "2_2") (pintype "passive"))
      (node (ref "R20") (pin "1") (pinfunction "1_1") (pintype "passive"))
      (node (ref "U5") (pin "16") (pinfunction "GPIO7_WAKEUP_16") (pintype "bidirectional"))
    )
    (net (code "41") (name "/PWM1") (class "Default")
      (node (ref "Q5") (pin "1") (pinfunction "G_1") (pintype "passive"))
      (node (ref "R49") (pin "2") (pinfunction "2_2") (pintype "passive"))
    )
    (net (code "42") (name "/PWM2") (class "Default")
      (node (ref "Q4") (pin "1") (pinfunction "G_1") (pintype "passive"))
      (node (ref "R48") (pin "2") (pinfunction "2_2") (pintype "passive"))
    )
    (net (code "43") (name "/SPI3_CS") (class "Default")
      (node (ref "U5") (pin "4") (pinfunction "ISOLm_NCS_4") (pintype "bidirectional"))
    )
    (net (code "44") (name "/SPI3_MISO") (class "Default")
      (node (ref "Q3") (pin "3") (pinfunction "D_3") (pintype "passive"))
      (node (ref "R12") (pin "1") (pinfunction "1_1") (pintype "passive"))
    )
    (net (code "45") (name "/SPI3_MOSI") (class "Default")
      (node (ref "U5") (pin "3") (pinfunction "ISOLp_SDI_3") (pintype "bidirectional"))
    )
    (net (code "46") (name "/SPI3_SCLK") (class "Default")
      (node (ref "U5") (pin "1") (pinfunction "GPIO8_SCK_1") (pintype "bidirectional"))
    )
    (net (code "47") (name "/THERM_P") (class "Default")
      (node (ref "R19") (pin "1") (pinfunction "1_1") (pintype "passive"))
      (node (ref "R20") (pin "2") (pinfunction "2_2") (pintype "passive"))
      (node (ref "R21") (pin "1") (pinfunction "1_1") (pintype "passive"))
    )
    (net (code "48") (name "/VBAT_CELL_P") (class "Default")
      (node (ref "C35") (pin "2") (pinfunction "2_2") (pintype "passive"))
      (node (ref "FB1") (pin "1") (pinfunction "1_1") (pintype "passive"))
      (node (ref "J7") (pin "1") (pinfunction "1_1") (pintype "passive"))
    )
    (net (code "49") (name "/VBAT_MINUS") (class "Default")
      (node (ref "Q4") (pin "3") (pinfunction "S_3") (pintype "passive"))
      (node (ref "R48") (pin "1") (pinfunction "1_1") (pintype "passive"))
    )
    (net (code "50") (name "GND") (class "Default")
      (node (ref "C31") (pin "1") (pinfunction "1_1") (pintype "passive"))
      (node (ref "C32") (pin "1") (pinfunction "1_1") (pintype "passive"))
      (node (ref "C33") (pin "1") (pinfunction "1_1") (pintype "passive"))
      (node (ref "C34") (pin "1") (pinfunction "1_1") (pintype "passive"))
      (node (ref "C35") (pin "1") (pinfunction "1_1") (pintype "passive"))
      (node (ref "C36") (pin "1") (pinfunction "1_1") (pintype "passive"))
      (node (ref "C38") (pin "1") (pinfunction "1_1") (pintype "passive"))
      (node (ref "C43") (pin "1") (pinfunction "1_1") (pintype "passive"))
      (node (ref "C44") (pin "1") (pinfunction "1_1") (pintype "passive"))
      (node (ref "C45") (pin "1") (pinfunction "1_1") (pintype "passive"))
      (node (ref "C46") (pin "1") (pinfunction "1_1") (pintype "passive"))
      (node (ref "C47") (pin "1") (pinfunction "1_1") (pintype "passive"))
      (node (ref "C48") (pin "1") (pinfunction "1_1") (pintype "passive"))
      (node (ref "C49") (pin "1") (pinfunction "1_1") (pintype "passive"))
      (node (ref "C50") (pin "1") (pinfunction "1_1") (pintype "passive"))
      (node (ref "CESD1") (pin "2") (pinfunction "2_2") (pintype "passive"))
      (node (ref "CESD10") (pin "2") (pinfunction "2_2") (pintype "passive"))
      (node (ref "CESD11") (pin "2") (pinfunction "2_2") (pintype "passive"))
      (node (ref "CESD12") (pin "2") (pinfunction "2_2") (pintype "passive"))
      (node (ref "CESD13") (pin "2") (pinfunction "2_2") (pintype "passive"))
      (node (ref "CESD14") (pin "1") (pinfunction "1_1") (pintype "passive"))
      (node (ref "CESD15") (pin "2") (pinfunction "2_2") (pintype "passive"))
      (node (ref "CESD16") (pin "1") (pinfunction "1_1") (pintype "passive"))
      (node (ref "CESD17") (pin "2") (pinfunction "2_2") (pintype "passive"))
      (node (ref "CESD2") (pin "2") (pinfunction "2_2") (pintype "passive"))
      (node (ref "CESD3") (pin "2") (pinfunction "2_2") (pintype "passive"))
      (node (ref "CESD4") (pin "2") (pinfunction "2_2") (pintype "passive"))
      (node (ref "CESD5") (pin "2") (pinfunction "2_2") (pintype "passive"))
      (node (ref "CESD6") (pin "2") (pinfunction "2_2") (pintype "passive"))
      (node (ref "CESD7") (pin "2") (pinfunction "2_2") (pintype "passive"))
      (node (ref "CESD8") (pin "2") (pinfunction "2_2") (pintype "passive"))
      (node (ref "CESD9") (pin "2") (pinfunction "2_2") (pintype "passive"))
      (node (ref "CREG1") (pin "1") (pinfunction "1_1") (pintype "passive"))
      (node (ref "CVCOM") (pin "1") (pinfunction "1_1") (pintype "passive"))
      (node (ref "D7") (pin "A") (pinfunction "A_A") (pintype "passive"))
      (node (ref "D8") (pin "2") (pinfunction "A_2") (pintype "passive"))
      (node (ref "J7") (pin "17") (pinfunction "17_17") (pintype "passive"))
      (node (ref "J7") (pin "18") (pinfunction "18_18") (pintype "passive"))
      (node (ref "J7") (pin "22") (pinfunction "22_22") (pintype "passive"))
      (node (ref "J7") (pin "24") (pinfunction "24_24") (pintype "passive"))
      (node (ref "J7") (pin "26") (pinfunction "26_26") (pintype "passive"))
      (node (ref "J7") (pin "28") (pinfunction "28_28") (pintype "passive"))
      (node (ref "MHOT") (pin "1") (pinfunction "S_1") (pintype "input"))
      (node (ref "MHOT") (pin "2") (pinfunction "S_2") (pintype "input"))
      (node (ref "MHOT") (pin "3") (pinfunction "S_3") (pintype "input"))
      (node (ref "MHOT") (pin "5") (pinfunction "D_5") (pintype "input"))
      (node (ref "MHOT") (pin "6") (pinfunction "D_6") (pintype "input"))
      (node (ref "MHOT") (pin "7") (pinfunction "D_7") (pintype "input"))
      (node (ref "MHOT") (pin "8") (pinfunction "D_8") (pintype "input"))
      (node (ref "R21") (pin "2") (pinfunction "2_2") (pintype "passive"))
      (node (ref "R23") (pin "1") (pinfunction "1_1") (pintype "passive"))
      (node (ref "R23") (pin "2") (pinfunction "2_2") (pintype "passive"))
      (node (ref "R24") (pin "1") (pinfunction "1_1") (pintype "passive"))
      (node (ref "R26") (pin "1") (pinfunction "1_1") (pintype "passive"))
      (node (ref "R27") (pin "1") (pinfunction "1_1") (pintype "passive"))
      (node (ref "U5") (pin "22") (pinfunction "AGND_22") (pintype "passive"))
      (node (ref "U5") (pin "25") (pinfunction "GNDREF_25") (pintype "passive"))
      (node (ref "U5") (pin "6") (pinfunction "CGND_6") (pintype "passive"))
      (node (ref "U5") (pin "65") (pinfunction "GNDEP_65") (pintype "passive"))
      (node (ref "U5") (pin "9") (pinfunction "DGND_9") (pintype "passive"))
    )
    (net (code "51") (name "Net-(FBSNS1-Pad2)") (class "Default")
      (node (ref "FBSNS1") (pin "2") (pinfunction "2_2") (pintype "passive"))
      (node (ref "RDRV1") (pin "1") (pinfunction "1_1") (pintype "passive"))
      (node (ref "RLPF1") (pin "1") (pinfunction "1_1") (pintype "passive"))
      (node (ref "TPC14") (pin "1") (pinfunction "1_1") (pintype "passive"))
    )
    (net (code "52") (name "Net-(FBSNS3-Pad2)") (class "Default")
      (node (ref "FBSNS3") (pin "2") (pinfunction "2_2") (pintype "passive"))
      (node (ref "RDRV2") (pin "1") (pinfunction "1_1") (pintype "passive"))
      (node (ref "RDRV3") (pin "1") (pinfunction "1_1") (pintype "passive"))
      (node (ref "RLPF3") (pin "1") (pinfunction "1_1") (pintype "passive"))
      (node (ref "TPC12") (pin "1") (pinfunction "1_1") (pintype "passive"))
    )
    (net (code "53") (name "Net-(FBSNS5-Pad2)") (class "Default")
      (node (ref "FBSNS5") (pin "2") (pinfunction "2_2") (pintype "passive"))
      (node (ref "RDRV4") (pin "1") (pinfunction "1_1") (pintype "passive"))
      (node (ref "RDRV5") (pin "1") (pinfunction "1_1") (pintype "passive"))
      (node (ref "RLPF5") (pin "1") (pinfunction "1_1") (pintype "passive"))
      (node (ref "TPC10") (pin "1") (pinfunction "1_1") (pintype "passive"))
    )
    (net (code "54") (name "Net-(FBSNS7-Pad2)") (class "Default")
      (node (ref "FBSNS7") (pin "2") (pinfunction "2_2") (pintype "passive"))
      (node (ref "RDRV6") (pin "1") (pinfunction "1_1") (pintype "passive"))
      (node (ref "RDRV7") (pin "1") (pinfunction "1_1") (pintype "passive"))
      (node (ref "RLPF7") (pin "1") (pinfunction "1_1") (pintype "passive"))
      (node (ref "TPC8") (pin "1") (pinfunction "1_1") (pintype "passive"))
    )
    (net (code "55") (name "Net-(FBSNS9-Pad2)") (class "Default")
      (node (ref "FBSNS9") (pin "2") (pinfunction "2_2") (pintype "passive"))
      (node (ref "RDRV8") (pin "1") (pinfunction "1_1") (pintype "passive"))
      (node (ref "RDRV9") (pin "1") (pinfunction "1_1") (pintype "passive"))
      (node (ref "RLPF9") (pin "1") (pinfunction "1_1") (pintype "passive"))
      (node (ref "TPC6") (pin "1") (pinfunction "1_1") (pintype "passive"))
    )
    (net (code "56") (name "Net-(FBSNS11-Pad2)") (class "Default")
      (node (ref "FBSNS11") (pin "2") (pinfunction "2_2") (pintype "passive"))
      (node (ref "RDRV10") (pin "1") (pinfunction "1_1") (pintype "passive"))
      (node (ref "RDRV11") (pin "1") (pinfunction "1_1") (pintype "passive"))
      (node (ref "RLPF11") (pin "1") (pinfunction "1_1") (pintype "passive"))
      (node (ref "TPC4") (pin "1") (pinfunction "1_1") (pintype "passive"))
    )
    (net (code "57") (name "Net-(FBSNS13-Pad2)") (class "Default")
      (node (ref "FBSNS13") (pin "2") (pinfunction "2_2") (pintype "passive"))
      (node (ref "RDRV12") (pin "1") (pinfunction "1_1") (pintype "passive"))
      (node (ref "RDRV13") (pin "1") (pinfunction "1_1") (pintype "passive"))
      (node (ref "RLPF13") (pin "1") (pinfunction "1_1") (pintype "passive"))
      (node (ref "TPC2") (pin "1") (pinfunction "1_1") (pintype "passive"))
    )
    (net (code "58") (name "Net-(FBSNS15-Pad2)") (class "Default")
      (node (ref "FBSNS15") (pin "2") (pinfunction "2_2") (pintype "passive"))
      (node (ref "RDRV14") (pin "1") (pinfunction "1_1") (pintype "passive"))
      (node (ref "RLPF15") (pin "1") (pinfunction "1_1") (pintype "passive"))
      (node (ref "TPC0") (pin "1") (pinfunction "1_1") (pintype "passive"))
    )
    (net (code "59") (name "Net-(Q4-D)") (class "Default")
      (node (ref "Q4") (pin "4") (pinfunction "D_4") (pintype "passive"))
      (node (ref "Q5") (pin "4") (pinfunction "D_4") (pintype "passive"))
    )
    (net (code "60") (name "Net-(U5-B2_1)") (class "Default")
      (node (ref "FBSNS14") (pin "2") (pinfunction "2_2") (pintype "passive"))
      (node (ref "RLPF14") (pin "1") (pinfunction "1_1") (pintype "passive"))
      (node (ref "TPC1") (pin "1") (pinfunction "1_1") (pintype "passive"))
      (node (ref "U5") (pin "29") (pinfunction "B2_1_29") (pintype "output"))
    )
    (net (code "61") (name "Net-(U5-B4_3)") (class "Default")
      (node (ref "FBSNS12") (pin "2") (pinfunction "2_2") (pintype "passive"))
      (node (ref "RLPF12") (pin "1") (pinfunction "1_1") (pintype "passive"))
      (node (ref "TPC3") (pin "1") (pinfunction "1_1") (pintype "passive"))
      (node (ref "U5") (pin "34") (pinfunction "B4_3_34") (pintype "output"))
    )
    (net (code "62") (name "Net-(U5-B6_5)") (class "Default")
      (node (ref "FBSNS10") (pin "2") (pinfunction "2_2") (pintype "passive"))
      (node (ref "RLPF10") (pin "1") (pinfunction "1_1") (pintype "passive"))
      (node (ref "TPC5") (pin "1") (pinfunction "1_1") (pintype "passive"))
      (node (ref "U5") (pin "39") (pinfunction "B6_5_39") (pintype "output"))
    )
    (net (code "63") (name "Net-(U5-B8_7)") (class "Default")
      (node (ref "FBSNS8") (pin "2") (pinfunction "2_2") (pintype "passive"))
      (node (ref "RLPF8") (pin "1") (pinfunction "1_1") (pintype "passive"))
      (node (ref "TPC7") (pin "1") (pinfunction "1_1") (pintype "passive"))
      (node (ref "U5") (pin "44") (pinfunction "B8_7_44") (pintype "output"))
    )
    (net (code "64") (name "Net-(U5-B10_9)") (class "Default")
      (node (ref "FBSNS6") (pin "2") (pinfunction "2_2") (pintype "passive"))
      (node (ref "RLPF6") (pin "1") (pinfunction "1_1") (pintype "passive"))
      (node (ref "TPC9") (pin "1") (pinfunction "1_1") (pintype "passive"))
      (node (ref "U5") (pin "49") (pinfunction "B10_9_49") (pintype "output"))
    )
    (net (code "65") (name "Net-(U5-B12_11)") (class "Default")
      (node (ref "FBSNS4") (pin "2") (pinfunction "2_2") (pintype "passive"))
      (node (ref "RLPF4") (pin "1") (pinfunction "1_1") (pintype "passive"))
      (node (ref "TPC11") (pin "1") (pinfunction "1_1") (pintype "passive"))
      (node (ref "U5") (pin "54") (pinfunction "B12_11_54") (pintype "output"))
    )
    (net (code "66") (name "Net-(U5-B14_13)") (class "Default")
      (node (ref "FBSNS2") (pin "2") (pinfunction "2_2") (pintype "passive"))
      (node (ref "RLPF2") (pin "1") (pinfunction "1_1") (pintype "passive"))
      (node (ref "TPC13") (pin "1") (pinfunction "1_1") (pintype "passive"))
      (node (ref "U5") (pin "59") (pinfunction "B14_13_59") (pintype "output"))
    )
    (net (code "67") (name "Net-(U5-C0)") (class "Default")
      (node (ref "CLPF14") (pin "1") (pinfunction "1_1") (pintype "passive"))
      (node (ref "RLPF15") (pin "2") (pinfunction "2_2") (pintype "passive"))
      (node (ref "U5") (pin "26") (pinfunction "C0_26") (pintype "input"))
    )
    (net (code "68") (name "Net-(U5-C1)") (class "Default")
      (node (ref "CLPF13") (pin "1") (pinfunction "1_1") (pintype "passive"))
      (node (ref "CLPF14") (pin "2") (pinfunction "2_2") (pintype "passive"))
      (node (ref "RLPF14") (pin "2") (pinfunction "2_2") (pintype "passive"))
      (node (ref "U5") (pin "27") (pinfunction "C1_27") (pintype "input"))
    )
    (net (code "69") (name "Net-(U5-C2)") (class "Default")
      (node (ref "CLPF12") (pin "1") (pinfunction "1_1") (pintype "passive"))
      (node (ref "CLPF13") (pin "2") (pinfunction "2_2") (pintype "passive"))
      (node (ref "RLPF13") (pin "2") (pinfunction "2_2") (pintype "passive"))
      (node (ref "U5") (pin "31") (pinfunction "C2_31") (pintype "input"))
    )
    (net (code "70") (name "Net-(U5-C3)") (class "Default")
      (node (ref "CLPF11") (pin "1") (pinfunction "1_1") (pintype "passive"))
      (node (ref "CLPF12") (pin "2") (pinfunction "2_2") (pintype "passive"))
      (node (ref "RLPF12") (pin "2") (pinfunction "2_2") (pintype "passive"))
      (node (ref "U5") (pin "32") (pinfunction "C3_32") (pintype "input"))
    )
    (net (code "71") (name "Net-(U5-C4)") (class "Default")
      (node (ref "CLPF10") (pin "1") (pinfunction "1_1") (pintype "passive"))
      (node (ref "CLPF11") (pin "2") (pinfunction "2_2") (pintype "passive"))
      (node (ref "RLPF11") (pin "2") (pinfunction "2_2") (pintype "passive"))
      (node (ref "U5") (pin "36") (pinfunction "C4_36") (pintype "input"))
    )
    (net (code "72") (name "Net-(U5-C5)") (class "Default")
      (node (ref "CLPF10") (pin "2") (pinfunction "2_2") (pintype "passive"))
      (node (ref "CLPF9") (pin "1") (pinfunction "1_1") (pintype "passive"))
      (node (ref "RLPF10") (pin "2") (pinfunction "2_2") (pintype "passive"))
      (node (ref "U5") (pin "37") (pinfunction "C5_37") (pintype "input"))
    )
    (net (code "73") (name "Net-(U5-C6)") (class "Default")
      (node (ref "CLPF8") (pin "1") (pinfunction "1_1") (pintype "passive"))
      (node (ref "CLPF9") (pin "2") (pinfunction "2_2") (pintype "passive"))
      (node (ref "RLPF9") (pin "2") (pinfunction "2_2") (pintype "passive"))
      (node (ref "U5") (pin "41") (pinfunction "C6_41") (pintype "input"))
    )
    (net (code "74") (name "Net-(U5-C7)") (class "Default")
      (node (ref "CLPF7") (pin "1") (pinfunction "1_1") (pintype "passive"))
      (node (ref "CLPF8") (pin "2") (pinfunction "2_2") (pintype "passive"))
      (node (ref "RLPF8") (pin "2") (pinfunction "2_2") (pintype "passive"))
      (node (ref "U5") (pin "42") (pinfunction "C7_42") (pintype "input"))
    )
    (net (code "75") (name "Net-(U5-C8)") (class "Default")
      (node (ref "CLPF6") (pin "1") (pinfunction "1_1") (pintype "passive"))
      (node (ref "CLPF7") (pin "2") (pinfunction "2_2") (pintype "passive"))
      (node (ref "RLPF7") (pin "2") (pinfunction "2_2") (pintype "passive"))
      (node (ref "U5") (pin "46") (pinfunction "C8_46") (pintype "input"))
    )
    (net (code "76") (name "Net-(U5-C9)") (class "Default")
      (node (ref "CLPF5") (pin "1") (pinfunction "1_1") (pintype "passive"))
      (node (ref "CLPF6") (pin "2") (pinfunction "2_2") (pintype "passive"))
      (node (ref "RLPF6") (pin "2") (pinfunction "2_2") (pintype "passive"))
      (node (ref "U5") (pin "47") (pinfunction "C9_47") (pintype "input"))
    )
    (net (code "77") (name "Net-(U5-C10)") (class "Default")
      (node (ref "CLPF4") (pin "1") (pinfunction "1_1") (pintype "passive"))
      (node (ref "CLPF5") (pin "2") (pinfunction "2_2") (pintype "passive"))
      (node (ref "RLPF5") (pin "2") (pinfunction "2_2") (pintype "passive"))
      (node (ref "U5") (pin "51") (pinfunction "C10_51") (pintype "input"))
    )
    (net (code "78") (name "Net-(U5-C11)") (class "Default")
      (node (ref "CLPF3") (pin "1") (pinfunction "1_1") (pintype "passive"))
      (node (ref "CLPF4") (pin "2") (pinfunction "2_2") (pintype "passive"))
      (node (ref "RLPF4") (pin "2") (pinfunction "2_2") (pintype "passive"))
      (node (ref "U5") (pin "52") (pinfunction "C11_52") (pintype "input"))
    )
    (net (code "79") (name "Net-(U5-C12)") (class "Default")
      (node (ref "CLPF2") (pin "1") (pinfunction "1_1") (pintype "passive"))
      (node (ref "CLPF3") (pin "2") (pinfunction "2_2") (pintype "passive"))
      (node (ref "RLPF3") (pin "2") (pinfunction "2_2") (pintype "passive"))
      (node (ref "U5") (pin "56") (pinfunction "C12_56") (pintype "input"))
    )
    (net (code "80") (name "Net-(U5-C13)") (class "Default")
      (node (ref "CLPF1") (pin "1") (pinfunction "1_1") (pintype "passive"))
      (node (ref "CLPF2") (pin "2") (pinfunction "2_2") (pintype "passive"))
      (node (ref "RLPF2") (pin "2") (pinfunction "2_2") (pintype "passive"))
      (node (ref "U5") (pin "57") (pinfunction "C13_57") (pintype "input"))
    )
    (net (code "81") (name "Net-(U5-C14)") (class "Default")
      (node (ref "CLPF1") (pin "2") (pinfunction "2_2") (pintype "passive"))
      (node (ref "RLPF1") (pin "2") (pinfunction "2_2") (pintype "passive"))
      (node (ref "U5") (pin "61") (pinfunction "C14_61") (pintype "input"))
    )
    (net (code "82") (name "Net-(U5-ISOHm)") (class "Default")
      (node (ref "U5") (pin "7") (pinfunction "ISOHp_7") (pintype "bidirectional"))
      (node (ref "U5") (pin "8") (pinfunction "ISOHm_8") (pintype "bidirectional"))
    )
    (net (code "83") (name "Net-(U5-S1)") (class "Default")
      (node (ref "RDRV14") (pin "2") (pinfunction "2_2") (pintype "passive"))
      (node (ref "U5") (pin "28") (pinfunction "S1_28") (pintype "output"))
    )
    (net (code "84") (name "Net-(U5-S2)") (class "Default")
      (node (ref "RDRV13") (pin "2") (pinfunction "2_2") (pintype "passive"))
      (node (ref "U5") (pin "30") (pinfunction "S2_30") (pintype "output"))
    )
    (net (code "85") (name "Net-(U5-S3)") (class "Default")
      (node (ref "RDRV12") (pin "2") (pinfunction "2_2") (pintype "passive"))
      (node (ref "U5") (pin "33") (pinfunction "S3_33") (pintype "output"))
    )
    (net (code "86") (name "Net-(U5-S4)") (class "Default")
      (node (ref "RDRV11") (pin "2") (pinfunction "2_2") (pintype "passive"))
      (node (ref "U5") (pin "35") (pinfunction "S4_35") (pintype "output"))
    )
    (net (code "87") (name "Net-(U5-S5)") (class "Default")
      (node (ref "RDRV10") (pin "2") (pinfunction "2_2") (pintype "passive"))
      (node (ref "U5") (pin "38") (pinfunction "S5_38") (pintype "output"))
    )
    (net (code "88") (name "Net-(U5-S6)") (class "Default")
      (node (ref "RDRV9") (pin "2") (pinfunction "2_2") (pintype "passive"))
      (node (ref "U5") (pin "40") (pinfunction "S6_40") (pintype "output"))
    )
    (net (code "89") (name "Net-(U5-S7)") (class "Default")
      (node (ref "RDRV8") (pin "2") (pinfunction "2_2") (pintype "passive"))
      (node (ref "U5") (pin "43") (pinfunction "S7_43") (pintype "output"))
    )
    (net (code "90") (name "Net-(U5-S8)") (class "Default")
      (node (ref "RDRV7") (pin "2") (pinfunction "2_2") (pintype "passive"))
      (node (ref "U5") (pin "45") (pinfunction "S8_45") (pintype "output"))
    )
    (net (code "91") (name "Net-(U5-S9)") (class "Default")
      (node (ref "RDRV6") (pin "2") (pinfunction "2_2") (pintype "passive"))
      (node (ref "U5") (pin "48") (pinfunction "S9_48") (pintype "output"))
    )
    (net (code "92") (name "Net-(U5-S10)") (class "Default")
      (node (ref "RDRV5") (pin "2") (pinfunction "2_2") (pintype "passive"))
      (node (ref "U5") (pin "50") (pinfunction "S10_50") (pintype "output"))
    )
    (net (code "93") (name "Net-(U5-S11)") (class "Default")
      (node (ref "RDRV4") (pin "2") (pinfunction "2_2") (pintype "passive"))
      (node (ref "U5") (pin "53") (pinfunction "S11_53") (pintype "output"))
    )
    (net (code "94") (name "Net-(U5-S12)") (class "Default")
      (node (ref "RDRV3") (pin "2") (pinfunction "2_2") (pintype "passive"))
      (node (ref "U5") (pin "55") (pinfunction "S12_55") (pintype "output"))
    )
    (net (code "95") (name "Net-(U5-S13)") (class "Default")
      (node (ref "RDRV2") (pin "2") (pinfunction "2_2") (pintype "passive"))
      (node (ref "U5") (pin "58") (pinfunction "S13_58") (pintype "output"))
    )
    (net (code "96") (name "Net-(U5-S14)") (class "Default")
      (node (ref "RDRV1") (pin "2") (pinfunction "2_2") (pintype "passive"))
      (node (ref "U5") (pin "60") (pinfunction "S14_60") (pintype "output"))
    )
    (net (code "97") (name "VREG") (class "Default")
      (node (ref "CREG1") (pin "2") (pinfunction "2_2") (pintype "passive"))
      (node (ref "J8") (pin "3") (pinfunction "3_3") (pintype "passive"))
      (node (ref "Q2") (pin "1") (pinfunction "S_1") (pintype "passive"))
      (node (ref "Q2") (pin "2") (pinfunction "S_2") (pintype "passive"))
      (node (ref "Q2") (pin "3") (pinfunction "S_3") (pintype "passive"))
      (node (ref "TPVREG") (pin "1") (pinfunction "1_1") (pintype "passive"))
      (node (ref "U5") (pin "18") (pinfunction "VREG_18") (pintype "power_in"))
    )
    (net (code "98") (name "unconnected-(J7-Pad19)") (class "Default")
      (node (ref "J7") (pin "19") (pinfunction "19_19") (pintype "passive+no_connect"))
    )
    (net (code "99") (name "unconnected-(U5-VANA-Pad21)") (class "Default")
      (node (ref "U5") (pin "21") (pinfunction "VANA_21") (pintype "power_in+no_connect"))
    )
    (net (code "100") (name "unconnected-(U5-VTREF-Pad19)") (class "Default")
      (node (ref "U5") (pin "19") (pinfunction "VTREF_19") (pintype "power_in+no_connect"))
    )
  )
)
